# mmu6100x.net
KiCad netlist of a schematic drawn in EAGLE
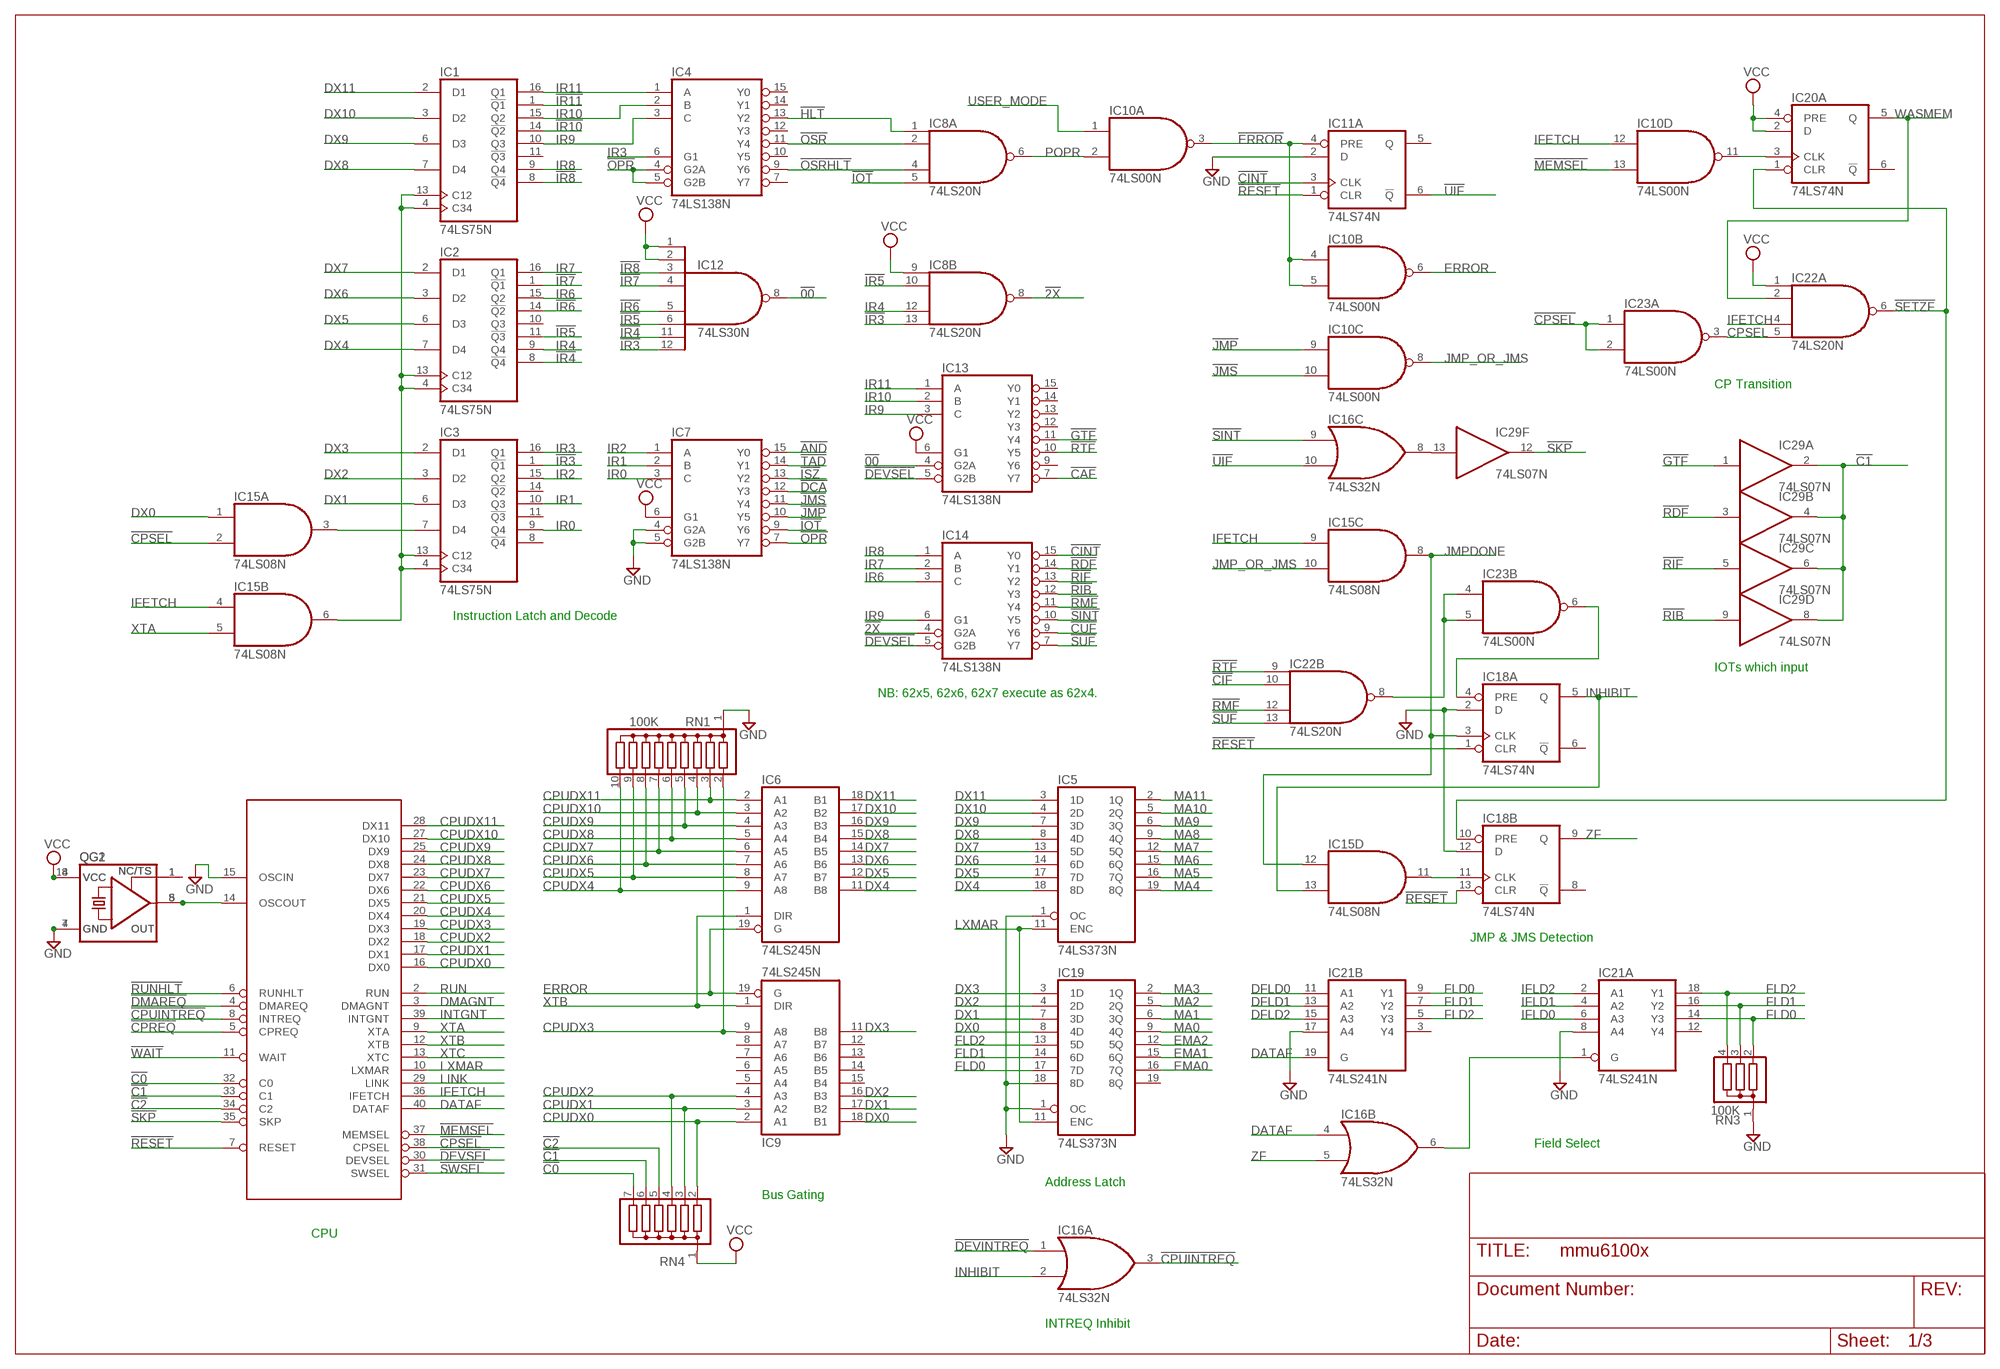
[diagram p0: schematic, sheet 1]
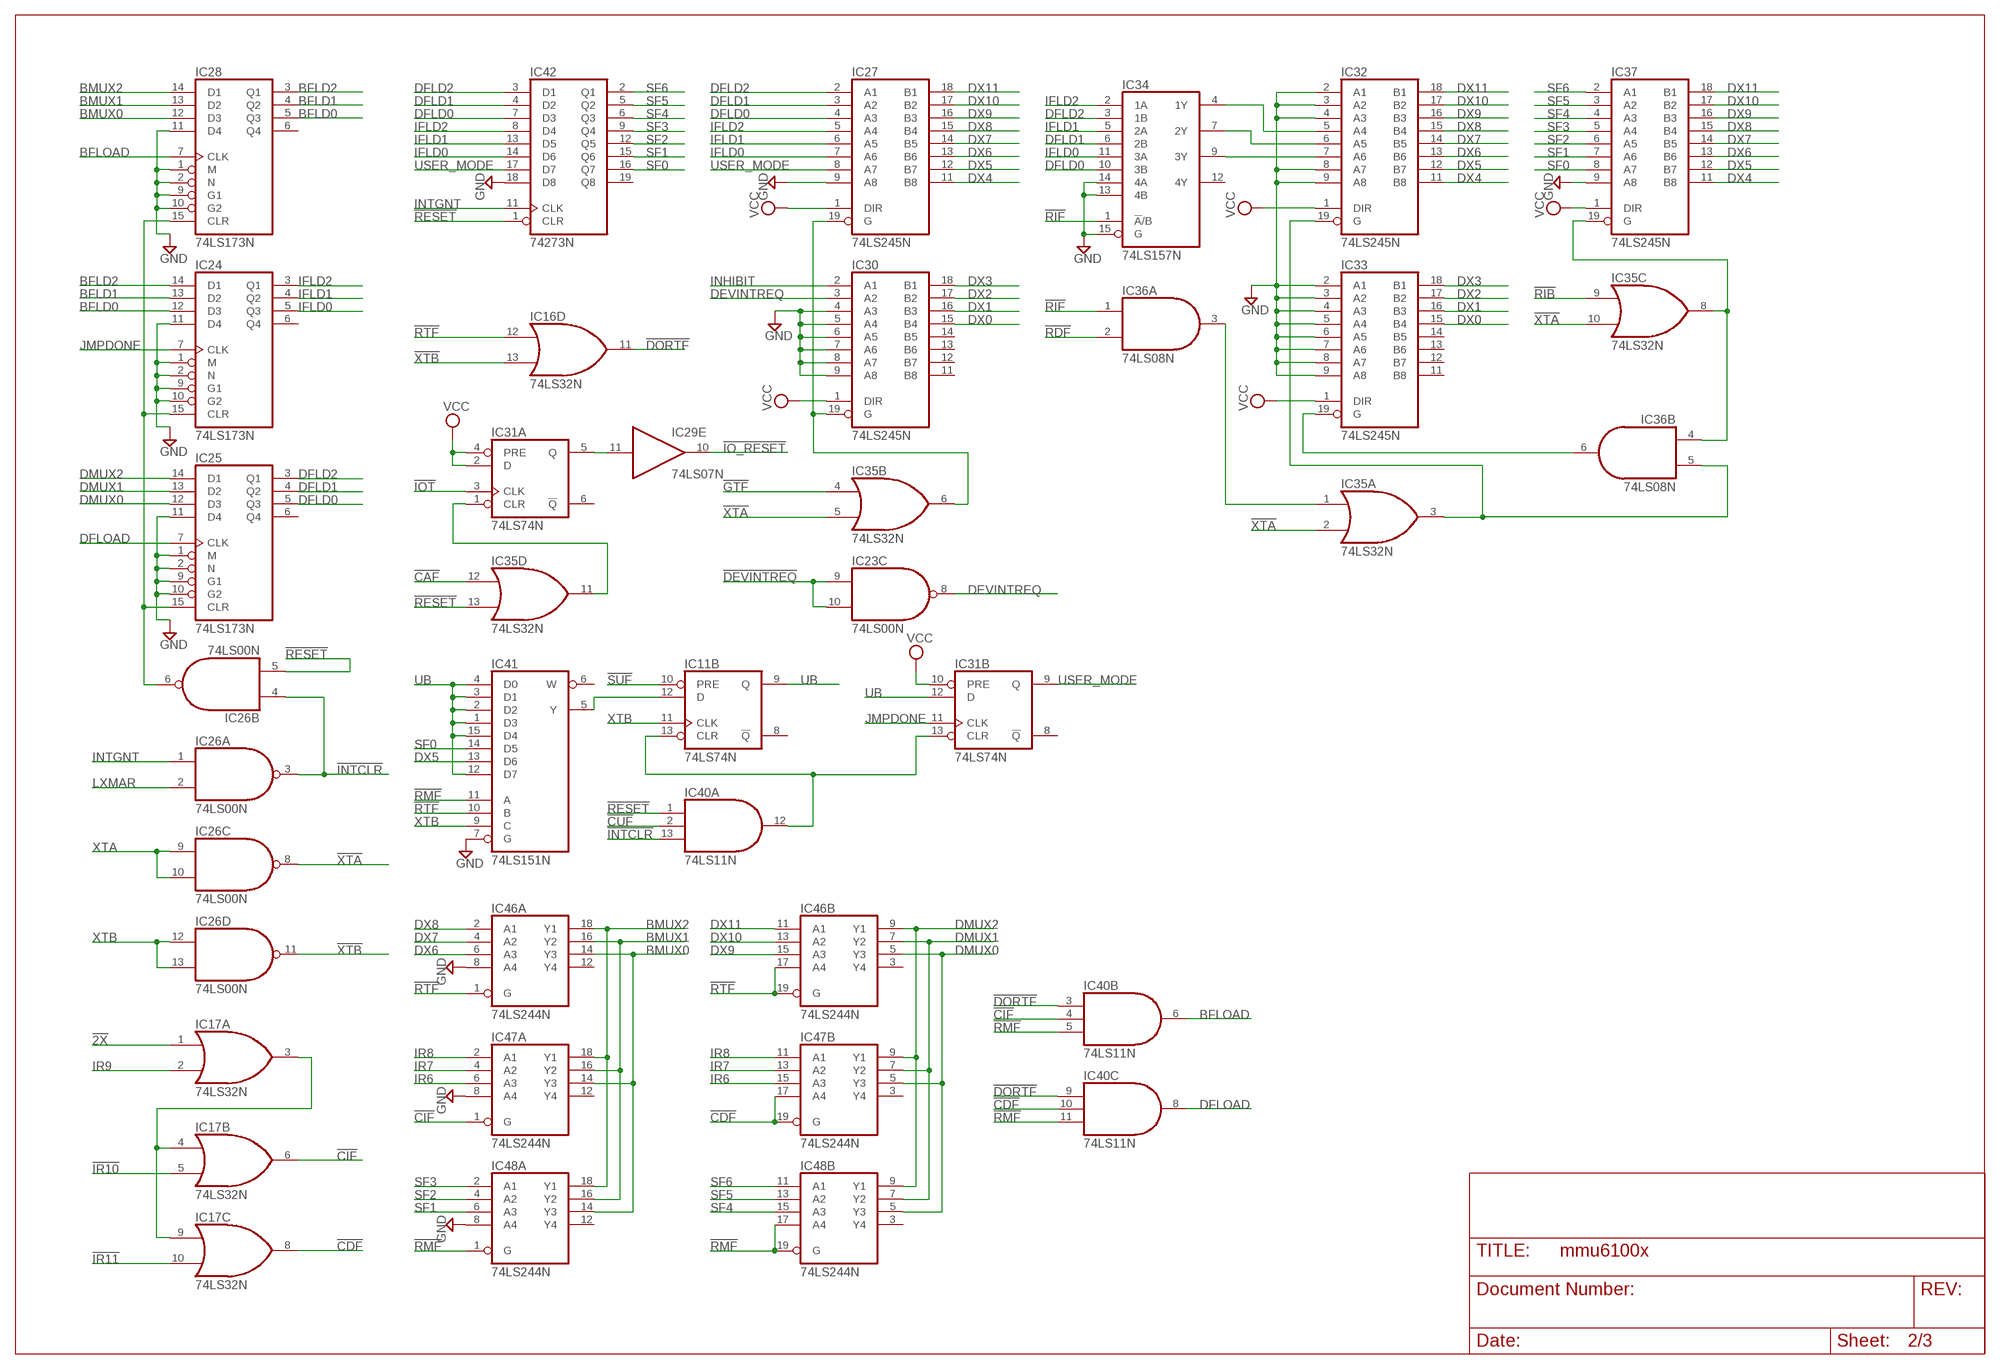
[diagram p1: schematic, sheet 2]
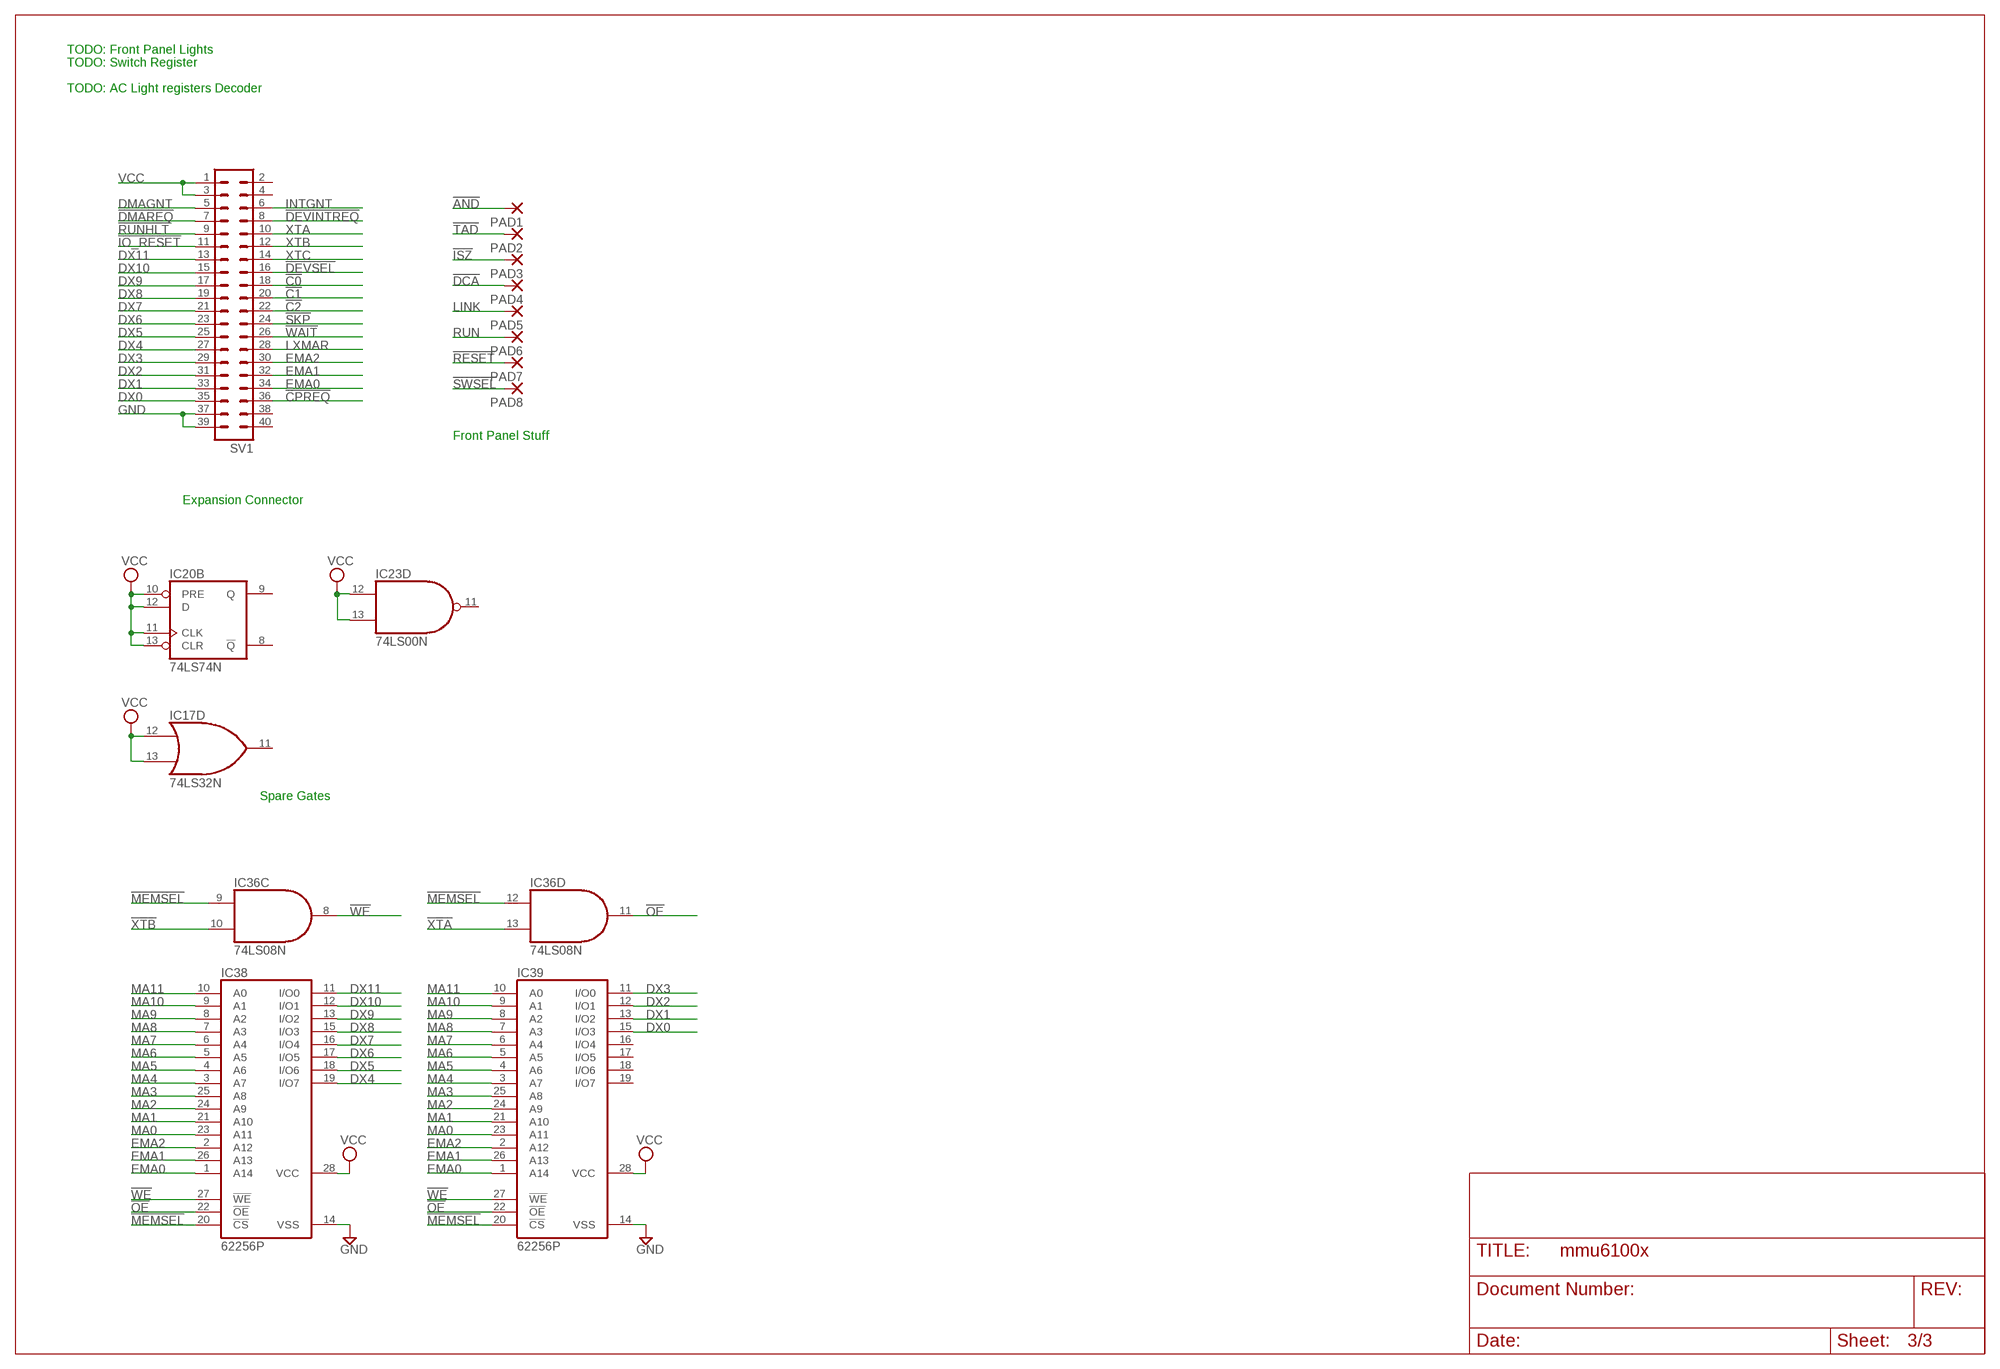
[diagram p2: schematic, sheet 3]

(export (version "E")
  (design (tool "Eeschema 10.0.6"))
  (components
    (comp (ref "IC11")
      (value "74LS74N")
      (footprint "eagle-import:DIL14")
      (libsource (lib "eagle-import") (part "7474NLS"))
    )
    (comp (ref "IC16")
      (value "74LS32N")
      (footprint "eagle-import:DIL14")
      (libsource (lib "eagle-import") (part "7432NLS"))
    )
    (comp (ref "IC17")
      (value "74LS32N")
      (footprint "eagle-import:DIL14")
      (libsource (lib "eagle-import") (part "7432NLS"))
    )
    (comp (ref "IC23")
      (value "74LS00N")
      (footprint "eagle-import:DIL14")
      (libsource (lib "eagle-import") (part "7400NLS"))
    )
    (comp (ref "IC24")
      (value "74LS173N")
      (footprint "eagle-import:DIL16")
      (libsource (lib "eagle-import") (part "74173NLS"))
    )
    (comp (ref "IC25")
      (value "74LS173N")
      (footprint "eagle-import:DIL16")
      (libsource (lib "eagle-import") (part "74173NLS"))
    )
    (comp (ref "IC26")
      (value "74LS00N")
      (footprint "eagle-import:DIL14")
      (libsource (lib "eagle-import") (part "7400NLS"))
    )
    (comp (ref "IC27")
      (value "74LS245N")
      (footprint "eagle-import:DIL20")
      (libsource (lib "eagle-import") (part "74245NLS"))
    )
    (comp (ref "IC28")
      (value "74LS173N")
      (footprint "eagle-import:DIL16")
      (libsource (lib "eagle-import") (part "74173NLS"))
    )
    (comp (ref "IC29")
      (value "74LS07N")
      (footprint "eagle-import:DIL14")
      (libsource (lib "eagle-import") (part "7407NLS"))
    )
    (comp (ref "IC30")
      (value "74LS245N")
      (footprint "eagle-import:DIL20")
      (libsource (lib "eagle-import") (part "74245NLS"))
    )
    (comp (ref "IC31")
      (value "74LS74N")
      (footprint "eagle-import:DIL14")
      (libsource (lib "eagle-import") (part "7474NLS"))
    )
    (comp (ref "IC32")
      (value "74LS245N")
      (footprint "eagle-import:DIL20")
      (libsource (lib "eagle-import") (part "74245NLS"))
    )
    (comp (ref "IC33")
      (value "74LS245N")
      (footprint "eagle-import:DIL20")
      (libsource (lib "eagle-import") (part "74245NLS"))
    )
    (comp (ref "IC34")
      (value "74LS157N")
      (footprint "eagle-import:DIL16")
      (libsource (lib "eagle-import") (part "74157NLS"))
    )
    (comp (ref "IC35")
      (value "74LS32N")
      (footprint "eagle-import:DIL14")
      (libsource (lib "eagle-import") (part "7432NLS"))
    )
    (comp (ref "IC36")
      (value "74LS08N")
      (footprint "eagle-import:DIL14")
      (libsource (lib "eagle-import") (part "7408NLS"))
    )
    (comp (ref "IC37")
      (value "74LS245N")
      (footprint "eagle-import:DIL20")
      (libsource (lib "eagle-import") (part "74245NLS"))
    )
    (comp (ref "IC40")
      (value "74LS11N")
      (footprint "eagle-import:DIL14")
      (libsource (lib "eagle-import") (part "7411NLS"))
    )
    (comp (ref "IC41")
      (value "74LS151N")
      (footprint "eagle-import:DIL16")
      (libsource (lib "eagle-import") (part "74151NLS"))
    )
    (comp (ref "IC42")
      (value "74273N")
      (footprint "eagle-import:DIL20")
      (libsource (lib "eagle-import") (part "74273N"))
    )
    (comp (ref "IC46")
      (value "74LS244N")
      (footprint "eagle-import:DIL20")
      (libsource (lib "eagle-import") (part "74244NLS"))
    )
    (comp (ref "IC47")
      (value "74LS244N")
      (footprint "eagle-import:DIL20")
      (libsource (lib "eagle-import") (part "74244NLS"))
    )
    (comp (ref "IC48")
      (value "74LS244N")
      (footprint "eagle-import:DIL20")
      (libsource (lib "eagle-import") (part "74244NLS"))
    )
    (comp (ref "IC20")
      (value "74LS74N")
      (footprint "eagle-import:DIL14")
      (libsource (lib "eagle-import") (part "7474NLS"))
    )
    (comp (ref "IC38")
      (value "62256P")
      (footprint "eagle-import:DIL28-6")
      (libsource (lib "eagle-import") (part "62256P"))
    )
    (comp (ref "IC39")
      (value "62256P")
      (footprint "eagle-import:DIL28-6")
      (libsource (lib "eagle-import") (part "62256P"))
    )
    (comp (ref "PAD1")
      (value "2,15/1,0")
      (footprint "eagle-import:2,15_1,0")
      (libsource (lib "eagle-import") (part "2,15/1,0"))
    )
    (comp (ref "PAD2")
      (value "2,15/1,0")
      (footprint "eagle-import:2,15_1,0")
      (libsource (lib "eagle-import") (part "2,15/1,0"))
    )
    (comp (ref "PAD3")
      (value "2,15/1,0")
      (footprint "eagle-import:2,15_1,0")
      (libsource (lib "eagle-import") (part "2,15/1,0"))
    )
    (comp (ref "PAD4")
      (value "2,15/1,0")
      (footprint "eagle-import:2,15_1,0")
      (libsource (lib "eagle-import") (part "2,15/1,0"))
    )
    (comp (ref "PAD5")
      (value "2,15/1,0")
      (footprint "eagle-import:2,15_1,0")
      (libsource (lib "eagle-import") (part "2,15/1,0"))
    )
    (comp (ref "PAD6")
      (value "2,15/1,0")
      (footprint "eagle-import:2,15_1,0")
      (libsource (lib "eagle-import") (part "2,15/1,0"))
    )
    (comp (ref "PAD7")
      (value "2,15/1,0")
      (footprint "eagle-import:2,15_1,0")
      (libsource (lib "eagle-import") (part "2,15/1,0"))
    )
    (comp (ref "PAD8")
      (value "2,15/1,0")
      (footprint "eagle-import:2,15_1,0")
      (libsource (lib "eagle-import") (part "2,15/1,0"))
    )
    (comp (ref "SV1")
      (value "MA20-2")
      (footprint "eagle-import:MA20-2")
      (libsource (lib "eagle-import") (part "MA20-2"))
    )
    (comp (ref "CPU")
      (value "IM6100")
      (footprint "eagle-import:DIL40")
      (libsource (lib "eagle-import") (part "IM6100"))
    )
    (comp (ref "IC1")
      (value "74LS75N")
      (footprint "eagle-import:DIL16")
      (libsource (lib "eagle-import") (part "7475NLS"))
    )
    (comp (ref "IC2")
      (value "74LS75N")
      (footprint "eagle-import:DIL16")
      (libsource (lib "eagle-import") (part "7475NLS"))
    )
    (comp (ref "IC3")
      (value "74LS75N")
      (footprint "eagle-import:DIL16")
      (libsource (lib "eagle-import") (part "7475NLS"))
    )
    (comp (ref "IC4")
      (value "74LS138N")
      (footprint "eagle-import:DIL16")
      (libsource (lib "eagle-import") (part "74138NLS"))
    )
    (comp (ref "IC5")
      (value "74LS373N")
      (footprint "eagle-import:DIL20")
      (libsource (lib "eagle-import") (part "74373NLS"))
    )
    (comp (ref "IC6")
      (value "74LS245N")
      (footprint "eagle-import:DIL20")
      (libsource (lib "eagle-import") (part "74245NLS"))
    )
    (comp (ref "IC7")
      (value "74LS138N")
      (footprint "eagle-import:DIL16")
      (libsource (lib "eagle-import") (part "74138NLS"))
    )
    (comp (ref "IC8")
      (value "74LS20N")
      (footprint "eagle-import:DIL14")
      (libsource (lib "eagle-import") (part "7420NLS"))
    )
    (comp (ref "IC9")
      (value "74LS245N")
      (footprint "eagle-import:DIL20")
      (libsource (lib "eagle-import") (part "74245NLS"))
    )
    (comp (ref "IC10")
      (value "74LS00N")
      (footprint "eagle-import:DIL14")
      (libsource (lib "eagle-import") (part "7400NLS"))
    )
    (comp (ref "IC12")
      (value "74LS30N")
      (footprint "eagle-import:DIL14")
      (libsource (lib "eagle-import") (part "7430NLS"))
    )
    (comp (ref "IC13")
      (value "74LS138N")
      (footprint "eagle-import:DIL16")
      (libsource (lib "eagle-import") (part "74138NLS"))
    )
    (comp (ref "IC14")
      (value "74LS138N")
      (footprint "eagle-import:DIL16")
      (libsource (lib "eagle-import") (part "74138NLS"))
    )
    (comp (ref "IC15")
      (value "74LS08N")
      (footprint "eagle-import:DIL14")
      (libsource (lib "eagle-import") (part "7408NLS"))
    )
    (comp (ref "IC18")
      (value "74LS74N")
      (footprint "eagle-import:DIL14")
      (libsource (lib "eagle-import") (part "7474NLS"))
    )
    (comp (ref "IC19")
      (value "74LS373N")
      (footprint "eagle-import:DIL20")
      (libsource (lib "eagle-import") (part "74373NLS"))
    )
    (comp (ref "IC21")
      (value "74LS241N")
      (footprint "eagle-import:DIL20")
      (libsource (lib "eagle-import") (part "74241NLS"))
    )
    (comp (ref "IC22")
      (value "74LS20N")
      (footprint "eagle-import:DIL14")
      (libsource (lib "eagle-import") (part "7420NLS"))
    )
    (comp (ref "QG1")
      (value "XO-8")
      (footprint "eagle-import:DIL08S")
      (libsource (lib "eagle-import") (part "XO-8"))
    )
    (comp (ref "QG2")
      (value "XO-14")
      (footprint "eagle-import:DIL14S")
      (libsource (lib "eagle-import") (part "XO-14"))
    )
    (comp (ref "RN1")
      (value "100K")
      (footprint "eagle-import:SIL10")
      (libsource (lib "eagle-import") (part "G09R"))
    )
    (comp (ref "RN3")
      (value "100K")
      (footprint "eagle-import:SIL4")
      (libsource (lib "eagle-import") (part "G03R"))
    )
    (comp (ref "RN4")
      (value "G06R")
      (footprint "eagle-import:SIL7")
      (libsource (lib "eagle-import") (part "G06R"))
    )
  )
  (nets
    (net (code "1") (name "BFLD0") (class "Default")
      (node (ref "IC24") (pin "12") (pinfunction "D3_12") (pintype "input"))
      (node (ref "IC28") (pin "5") (pinfunction "Q3_5") (pintype "tri_state"))
    )
    (net (code "2") (name "BFLD1") (class "Default")
      (node (ref "IC24") (pin "13") (pinfunction "D2_13") (pintype "input"))
      (node (ref "IC28") (pin "4") (pinfunction "Q2_4") (pintype "tri_state"))
    )
    (net (code "3") (name "BFLD2") (class "Default")
      (node (ref "IC24") (pin "14") (pinfunction "D1_14") (pintype "input"))
      (node (ref "IC28") (pin "3") (pinfunction "Q1_3") (pintype "tri_state"))
    )
    (net (code "4") (name "BFLOAD") (class "Default")
      (node (ref "IC28") (pin "7") (pinfunction "CLK_7") (pintype "input"))
      (node (ref "IC40") (pin "6") (pinfunction "O_6") (pintype "output"))
    )
    (net (code "5") (name "BMUX0") (class "Default")
      (node (ref "IC28") (pin "12") (pinfunction "D3_12") (pintype "input"))
      (node (ref "IC46") (pin "14") (pinfunction "Y3_14") (pintype "tri_state"))
      (node (ref "IC47") (pin "14") (pinfunction "Y3_14") (pintype "tri_state"))
      (node (ref "IC48") (pin "14") (pinfunction "Y3_14") (pintype "tri_state"))
    )
    (net (code "6") (name "BMUX1") (class "Default")
      (node (ref "IC28") (pin "13") (pinfunction "D2_13") (pintype "input"))
      (node (ref "IC46") (pin "16") (pinfunction "Y2_16") (pintype "tri_state"))
      (node (ref "IC47") (pin "16") (pinfunction "Y2_16") (pintype "tri_state"))
      (node (ref "IC48") (pin "16") (pinfunction "Y2_16") (pintype "tri_state"))
    )
    (net (code "7") (name "BMUX2") (class "Default")
      (node (ref "IC28") (pin "14") (pinfunction "D1_14") (pintype "input"))
      (node (ref "IC46") (pin "18") (pinfunction "Y1_18") (pintype "tri_state"))
      (node (ref "IC47") (pin "18") (pinfunction "Y1_18") (pintype "tri_state"))
      (node (ref "IC48") (pin "18") (pinfunction "Y1_18") (pintype "tri_state"))
    )
    (net (code "8") (name "CPSEL") (class "Default")
      (node (ref "IC22") (pin "5") (pinfunction "I3_5") (pintype "input"))
      (node (ref "IC23") (pin "3") (pinfunction "O_3") (pintype "output"))
    )
    (net (code "9") (name "CPUDX0") (class "Default")
      (node (ref "CPU") (pin "16") (pinfunction "DX0_16") (pintype "bidirectional"))
      (node (ref "IC9") (pin "2") (pinfunction "A1_2") (pintype "bidirectional"))
      (node (ref "RN4") (pin "2") (pinfunction "2_2") (pintype "passive"))
    )
    (net (code "10") (name "CPUDX1") (class "Default")
      (node (ref "CPU") (pin "17") (pinfunction "DX1_17") (pintype "bidirectional"))
      (node (ref "IC9") (pin "3") (pinfunction "A2_3") (pintype "bidirectional"))
      (node (ref "RN4") (pin "3") (pinfunction "3_3") (pintype "passive"))
    )
    (net (code "11") (name "CPUDX2") (class "Default")
      (node (ref "CPU") (pin "18") (pinfunction "DX2_18") (pintype "bidirectional"))
      (node (ref "IC9") (pin "4") (pinfunction "A3_4") (pintype "bidirectional"))
      (node (ref "RN4") (pin "4") (pinfunction "4_4") (pintype "passive"))
    )
    (net (code "12") (name "CPUDX3") (class "Default")
      (node (ref "CPU") (pin "19") (pinfunction "DX3_19") (pintype "bidirectional"))
      (node (ref "IC9") (pin "9") (pinfunction "A8_9") (pintype "bidirectional"))
      (node (ref "RN1") (pin "2") (pinfunction "2_2") (pintype "passive"))
    )
    (net (code "13") (name "CPUDX4") (class "Default")
      (node (ref "CPU") (pin "20") (pinfunction "DX4_20") (pintype "bidirectional"))
      (node (ref "IC6") (pin "9") (pinfunction "A8_9") (pintype "bidirectional"))
      (node (ref "RN1") (pin "10") (pinfunction "10_10") (pintype "passive"))
    )
    (net (code "14") (name "CPUDX5") (class "Default")
      (node (ref "CPU") (pin "21") (pinfunction "DX5_21") (pintype "bidirectional"))
      (node (ref "IC6") (pin "8") (pinfunction "A7_8") (pintype "bidirectional"))
      (node (ref "RN1") (pin "9") (pinfunction "9_9") (pintype "passive"))
    )
    (net (code "15") (name "CPUDX6") (class "Default")
      (node (ref "CPU") (pin "22") (pinfunction "DX6_22") (pintype "bidirectional"))
      (node (ref "IC6") (pin "7") (pinfunction "A6_7") (pintype "bidirectional"))
      (node (ref "RN1") (pin "8") (pinfunction "8_8") (pintype "passive"))
    )
    (net (code "16") (name "CPUDX7") (class "Default")
      (node (ref "CPU") (pin "23") (pinfunction "DX7_23") (pintype "bidirectional"))
      (node (ref "IC6") (pin "6") (pinfunction "A5_6") (pintype "bidirectional"))
      (node (ref "RN1") (pin "7") (pinfunction "7_7") (pintype "passive"))
    )
    (net (code "17") (name "CPUDX8") (class "Default")
      (node (ref "CPU") (pin "24") (pinfunction "DX8_24") (pintype "bidirectional"))
      (node (ref "IC6") (pin "5") (pinfunction "A4_5") (pintype "bidirectional"))
      (node (ref "RN1") (pin "6") (pinfunction "6_6") (pintype "passive"))
    )
    (net (code "18") (name "CPUDX9") (class "Default")
      (node (ref "CPU") (pin "25") (pinfunction "DX9_25") (pintype "bidirectional"))
      (node (ref "IC6") (pin "4") (pinfunction "A3_4") (pintype "bidirectional"))
      (node (ref "RN1") (pin "5") (pinfunction "5_5") (pintype "passive"))
    )
    (net (code "19") (name "CPUDX10") (class "Default")
      (node (ref "CPU") (pin "27") (pinfunction "DX10_27") (pintype "bidirectional"))
      (node (ref "IC6") (pin "3") (pinfunction "A2_3") (pintype "bidirectional"))
      (node (ref "RN1") (pin "4") (pinfunction "4_4") (pintype "passive"))
    )
    (net (code "20") (name "CPUDX11") (class "Default")
      (node (ref "CPU") (pin "28") (pinfunction "DX11_28") (pintype "bidirectional"))
      (node (ref "IC6") (pin "2") (pinfunction "A1_2") (pintype "bidirectional"))
      (node (ref "RN1") (pin "3") (pinfunction "3_3") (pintype "passive"))
    )
    (net (code "21") (name "DATAF") (class "Default")
      (node (ref "CPU") (pin "40") (pinfunction "DATAF_40") (pintype "output"))
      (node (ref "IC16") (pin "4") (pinfunction "I0_4") (pintype "input"))
      (node (ref "IC21") (pin "19") (pinfunction "G_19") (pintype "input"))
    )
    (net (code "22") (name "DEVINTREQ") (class "Default")
      (node (ref "IC23") (pin "8") (pinfunction "O_8") (pintype "output"))
      (node (ref "IC30") (pin "3") (pinfunction "A2_3") (pintype "bidirectional"))
    )
    (net (code "23") (name "DFLD0") (class "Default")
      (node (ref "IC21") (pin "11") (pinfunction "A1_11") (pintype "input"))
      (node (ref "IC25") (pin "5") (pinfunction "Q3_5") (pintype "tri_state"))
      (node (ref "IC27") (pin "4") (pinfunction "A3_4") (pintype "bidirectional"))
      (node (ref "IC34") (pin "10") (pinfunction "3B_10") (pintype "input"))
      (node (ref "IC42") (pin "7") (pinfunction "D3_7") (pintype "input"))
    )
    (net (code "24") (name "DFLD1") (class "Default")
      (node (ref "IC21") (pin "13") (pinfunction "A2_13") (pintype "input"))
      (node (ref "IC25") (pin "4") (pinfunction "Q2_4") (pintype "tri_state"))
      (node (ref "IC27") (pin "3") (pinfunction "A2_3") (pintype "bidirectional"))
      (node (ref "IC34") (pin "6") (pinfunction "2B_6") (pintype "input"))
      (node (ref "IC42") (pin "4") (pinfunction "D2_4") (pintype "input"))
    )
    (net (code "25") (name "DFLD2") (class "Default")
      (node (ref "IC21") (pin "15") (pinfunction "A3_15") (pintype "input"))
      (node (ref "IC25") (pin "3") (pinfunction "Q1_3") (pintype "tri_state"))
      (node (ref "IC27") (pin "2") (pinfunction "A1_2") (pintype "bidirectional"))
      (node (ref "IC34") (pin "3") (pinfunction "1B_3") (pintype "input"))
      (node (ref "IC42") (pin "3") (pinfunction "D1_3") (pintype "input"))
    )
    (net (code "26") (name "DFLOAD") (class "Default")
      (node (ref "IC25") (pin "7") (pinfunction "CLK_7") (pintype "input"))
      (node (ref "IC40") (pin "8") (pinfunction "O_8") (pintype "output"))
    )
    (net (code "27") (name "DMAGNT") (class "Default")
      (node (ref "CPU") (pin "3") (pinfunction "DMAGNT_3") (pintype "output"))
      (node (ref "SV1") (pin "5") (pinfunction "5_5") (pintype "passive"))
    )
    (net (code "28") (name "DMUX0") (class "Default")
      (node (ref "IC25") (pin "12") (pinfunction "D3_12") (pintype "input"))
      (node (ref "IC46") (pin "5") (pinfunction "Y3_5") (pintype "tri_state"))
      (node (ref "IC47") (pin "5") (pinfunction "Y3_5") (pintype "tri_state"))
      (node (ref "IC48") (pin "5") (pinfunction "Y3_5") (pintype "tri_state"))
    )
    (net (code "29") (name "DMUX1") (class "Default")
      (node (ref "IC25") (pin "13") (pinfunction "D2_13") (pintype "input"))
      (node (ref "IC46") (pin "7") (pinfunction "Y2_7") (pintype "tri_state"))
      (node (ref "IC47") (pin "7") (pinfunction "Y2_7") (pintype "tri_state"))
      (node (ref "IC48") (pin "7") (pinfunction "Y2_7") (pintype "tri_state"))
    )
    (net (code "30") (name "DMUX2") (class "Default")
      (node (ref "IC25") (pin "14") (pinfunction "D1_14") (pintype "input"))
      (node (ref "IC46") (pin "9") (pinfunction "Y1_9") (pintype "tri_state"))
      (node (ref "IC47") (pin "9") (pinfunction "Y1_9") (pintype "tri_state"))
      (node (ref "IC48") (pin "9") (pinfunction "Y1_9") (pintype "tri_state"))
    )
    (net (code "31") (name "DX0") (class "Default")
      (node (ref "IC15") (pin "1") (pinfunction "I0_1") (pintype "input"))
      (node (ref "IC19") (pin "8") (pinfunction "4D_8") (pintype "input"))
      (node (ref "IC30") (pin "15") (pinfunction "B4_15") (pintype "bidirectional"))
      (node (ref "IC33") (pin "15") (pinfunction "B4_15") (pintype "bidirectional"))
      (node (ref "IC39") (pin "15") (pinfunction "I/O3_15") (pintype "bidirectional"))
      (node (ref "IC9") (pin "18") (pinfunction "B1_18") (pintype "bidirectional"))
      (node (ref "SV1") (pin "35") (pinfunction "35_35") (pintype "passive"))
    )
    (net (code "32") (name "DX1") (class "Default")
      (node (ref "IC19") (pin "7") (pinfunction "3D_7") (pintype "input"))
      (node (ref "IC3") (pin "6") (pinfunction "D3_6") (pintype "input"))
      (node (ref "IC30") (pin "16") (pinfunction "B3_16") (pintype "bidirectional"))
      (node (ref "IC33") (pin "16") (pinfunction "B3_16") (pintype "bidirectional"))
      (node (ref "IC39") (pin "13") (pinfunction "I/O2_13") (pintype "bidirectional"))
      (node (ref "IC9") (pin "17") (pinfunction "B2_17") (pintype "bidirectional"))
      (node (ref "SV1") (pin "33") (pinfunction "33_33") (pintype "passive"))
    )
    (net (code "33") (name "DX2") (class "Default")
      (node (ref "IC19") (pin "4") (pinfunction "2D_4") (pintype "input"))
      (node (ref "IC3") (pin "3") (pinfunction "D2_3") (pintype "input"))
      (node (ref "IC30") (pin "17") (pinfunction "B2_17") (pintype "bidirectional"))
      (node (ref "IC33") (pin "17") (pinfunction "B2_17") (pintype "bidirectional"))
      (node (ref "IC39") (pin "12") (pinfunction "I/O1_12") (pintype "bidirectional"))
      (node (ref "IC9") (pin "16") (pinfunction "B3_16") (pintype "bidirectional"))
      (node (ref "SV1") (pin "31") (pinfunction "31_31") (pintype "passive"))
    )
    (net (code "34") (name "DX3") (class "Default")
      (node (ref "IC19") (pin "3") (pinfunction "1D_3") (pintype "input"))
      (node (ref "IC3") (pin "2") (pinfunction "D1_2") (pintype "input"))
      (node (ref "IC30") (pin "18") (pinfunction "B1_18") (pintype "bidirectional"))
      (node (ref "IC33") (pin "18") (pinfunction "B1_18") (pintype "bidirectional"))
      (node (ref "IC39") (pin "11") (pinfunction "I/O0_11") (pintype "bidirectional"))
      (node (ref "IC9") (pin "11") (pinfunction "B8_11") (pintype "bidirectional"))
      (node (ref "SV1") (pin "29") (pinfunction "29_29") (pintype "passive"))
    )
    (net (code "35") (name "DX4") (class "Default")
      (node (ref "IC2") (pin "7") (pinfunction "D4_7") (pintype "input"))
      (node (ref "IC27") (pin "11") (pinfunction "B8_11") (pintype "bidirectional"))
      (node (ref "IC32") (pin "11") (pinfunction "B8_11") (pintype "bidirectional"))
      (node (ref "IC37") (pin "11") (pinfunction "B8_11") (pintype "bidirectional"))
      (node (ref "IC38") (pin "19") (pinfunction "I/O7_19") (pintype "bidirectional"))
      (node (ref "IC5") (pin "18") (pinfunction "8D_18") (pintype "input"))
      (node (ref "IC6") (pin "11") (pinfunction "B8_11") (pintype "bidirectional"))
      (node (ref "SV1") (pin "27") (pinfunction "27_27") (pintype "passive"))
    )
    (net (code "36") (name "DX5") (class "Default")
      (node (ref "IC2") (pin "6") (pinfunction "D3_6") (pintype "input"))
      (node (ref "IC27") (pin "12") (pinfunction "B7_12") (pintype "bidirectional"))
      (node (ref "IC32") (pin "12") (pinfunction "B7_12") (pintype "bidirectional"))
      (node (ref "IC37") (pin "12") (pinfunction "B7_12") (pintype "bidirectional"))
      (node (ref "IC38") (pin "18") (pinfunction "I/O6_18") (pintype "bidirectional"))
      (node (ref "IC41") (pin "13") (pinfunction "D6_13") (pintype "input"))
      (node (ref "IC5") (pin "17") (pinfunction "7D_17") (pintype "input"))
      (node (ref "IC6") (pin "12") (pinfunction "B7_12") (pintype "bidirectional"))
      (node (ref "SV1") (pin "25") (pinfunction "25_25") (pintype "passive"))
    )
    (net (code "37") (name "DX6") (class "Default")
      (node (ref "IC2") (pin "3") (pinfunction "D2_3") (pintype "input"))
      (node (ref "IC27") (pin "13") (pinfunction "B6_13") (pintype "bidirectional"))
      (node (ref "IC32") (pin "13") (pinfunction "B6_13") (pintype "bidirectional"))
      (node (ref "IC37") (pin "13") (pinfunction "B6_13") (pintype "bidirectional"))
      (node (ref "IC38") (pin "17") (pinfunction "I/O5_17") (pintype "bidirectional"))
      (node (ref "IC46") (pin "6") (pinfunction "A3_6") (pintype "input"))
      (node (ref "IC5") (pin "14") (pinfunction "6D_14") (pintype "input"))
      (node (ref "IC6") (pin "13") (pinfunction "B6_13") (pintype "bidirectional"))
      (node (ref "SV1") (pin "23") (pinfunction "23_23") (pintype "passive"))
    )
    (net (code "38") (name "DX7") (class "Default")
      (node (ref "IC2") (pin "2") (pinfunction "D1_2") (pintype "input"))
      (node (ref "IC27") (pin "14") (pinfunction "B5_14") (pintype "bidirectional"))
      (node (ref "IC32") (pin "14") (pinfunction "B5_14") (pintype "bidirectional"))
      (node (ref "IC37") (pin "14") (pinfunction "B5_14") (pintype "bidirectional"))
      (node (ref "IC38") (pin "16") (pinfunction "I/O4_16") (pintype "bidirectional"))
      (node (ref "IC46") (pin "4") (pinfunction "A2_4") (pintype "input"))
      (node (ref "IC5") (pin "13") (pinfunction "5D_13") (pintype "input"))
      (node (ref "IC6") (pin "14") (pinfunction "B5_14") (pintype "bidirectional"))
      (node (ref "SV1") (pin "21") (pinfunction "21_21") (pintype "passive"))
    )
    (net (code "39") (name "DX8") (class "Default")
      (node (ref "IC1") (pin "7") (pinfunction "D4_7") (pintype "input"))
      (node (ref "IC27") (pin "15") (pinfunction "B4_15") (pintype "bidirectional"))
      (node (ref "IC32") (pin "15") (pinfunction "B4_15") (pintype "bidirectional"))
      (node (ref "IC37") (pin "15") (pinfunction "B4_15") (pintype "bidirectional"))
      (node (ref "IC38") (pin "15") (pinfunction "I/O3_15") (pintype "bidirectional"))
      (node (ref "IC46") (pin "2") (pinfunction "A1_2") (pintype "input"))
      (node (ref "IC5") (pin "8") (pinfunction "4D_8") (pintype "input"))
      (node (ref "IC6") (pin "15") (pinfunction "B4_15") (pintype "bidirectional"))
      (node (ref "SV1") (pin "19") (pinfunction "19_19") (pintype "passive"))
    )
    (net (code "40") (name "DX9") (class "Default")
      (node (ref "IC1") (pin "6") (pinfunction "D3_6") (pintype "input"))
      (node (ref "IC27") (pin "16") (pinfunction "B3_16") (pintype "bidirectional"))
      (node (ref "IC32") (pin "16") (pinfunction "B3_16") (pintype "bidirectional"))
      (node (ref "IC37") (pin "16") (pinfunction "B3_16") (pintype "bidirectional"))
      (node (ref "IC38") (pin "13") (pinfunction "I/O2_13") (pintype "bidirectional"))
      (node (ref "IC46") (pin "15") (pinfunction "A3_15") (pintype "input"))
      (node (ref "IC5") (pin "7") (pinfunction "3D_7") (pintype "input"))
      (node (ref "IC6") (pin "16") (pinfunction "B3_16") (pintype "bidirectional"))
      (node (ref "SV1") (pin "17") (pinfunction "17_17") (pintype "passive"))
    )
    (net (code "41") (name "DX10") (class "Default")
      (node (ref "IC1") (pin "3") (pinfunction "D2_3") (pintype "input"))
      (node (ref "IC27") (pin "17") (pinfunction "B2_17") (pintype "bidirectional"))
      (node (ref "IC32") (pin "17") (pinfunction "B2_17") (pintype "bidirectional"))
      (node (ref "IC37") (pin "17") (pinfunction "B2_17") (pintype "bidirectional"))
      (node (ref "IC38") (pin "12") (pinfunction "I/O1_12") (pintype "bidirectional"))
      (node (ref "IC46") (pin "13") (pinfunction "A2_13") (pintype "input"))
      (node (ref "IC5") (pin "4") (pinfunction "2D_4") (pintype "input"))
      (node (ref "IC6") (pin "17") (pinfunction "B2_17") (pintype "bidirectional"))
      (node (ref "SV1") (pin "15") (pinfunction "15_15") (pintype "passive"))
    )
    (net (code "42") (name "DX11") (class "Default")
      (node (ref "IC1") (pin "2") (pinfunction "D1_2") (pintype "input"))
      (node (ref "IC27") (pin "18") (pinfunction "B1_18") (pintype "bidirectional"))
      (node (ref "IC32") (pin "18") (pinfunction "B1_18") (pintype "bidirectional"))
      (node (ref "IC37") (pin "18") (pinfunction "B1_18") (pintype "bidirectional"))
      (node (ref "IC38") (pin "11") (pinfunction "I/O0_11") (pintype "bidirectional"))
      (node (ref "IC46") (pin "11") (pinfunction "A1_11") (pintype "input"))
      (node (ref "IC5") (pin "3") (pinfunction "1D_3") (pintype "input"))
      (node (ref "IC6") (pin "18") (pinfunction "B1_18") (pintype "bidirectional"))
      (node (ref "SV1") (pin "13") (pinfunction "13_13") (pintype "passive"))
    )
    (net (code "43") (name "EMA0") (class "Default")
      (node (ref "IC19") (pin "16") (pinfunction "7Q_16") (pintype "tri_state"))
      (node (ref "IC38") (pin "1") (pinfunction "A14_1") (pintype "input"))
      (node (ref "IC39") (pin "1") (pinfunction "A14_1") (pintype "input"))
      (node (ref "SV1") (pin "34") (pinfunction "34_34") (pintype "passive"))
    )
    (net (code "44") (name "EMA1") (class "Default")
      (node (ref "IC19") (pin "15") (pinfunction "6Q_15") (pintype "tri_state"))
      (node (ref "IC38") (pin "26") (pinfunction "A13_26") (pintype "input"))
      (node (ref "IC39") (pin "26") (pinfunction "A13_26") (pintype "input"))
      (node (ref "SV1") (pin "32") (pinfunction "32_32") (pintype "passive"))
    )
    (net (code "45") (name "EMA2") (class "Default")
      (node (ref "IC19") (pin "12") (pinfunction "5Q_12") (pintype "tri_state"))
      (node (ref "IC38") (pin "2") (pinfunction "A12_2") (pintype "input"))
      (node (ref "IC39") (pin "2") (pinfunction "A12_2") (pintype "input"))
      (node (ref "SV1") (pin "30") (pinfunction "30_30") (pintype "passive"))
    )
    (net (code "46") (name "ERROR") (class "Default")
      (node (ref "IC10") (pin "6") (pinfunction "O_6") (pintype "output"))
      (node (ref "IC6") (pin "19") (pinfunction "G_19") (pintype "input"))
      (node (ref "IC9") (pin "19") (pinfunction "G_19") (pintype "input"))
    )
    (net (code "47") (name "FLD0") (class "Default")
      (node (ref "IC19") (pin "17") (pinfunction "7D_17") (pintype "input"))
      (node (ref "IC21") (pin "14") (pinfunction "Y3_14") (pintype "tri_state"))
      (node (ref "IC21") (pin "9") (pinfunction "Y1_9") (pintype "tri_state"))
      (node (ref "RN3") (pin "2") (pinfunction "2_2") (pintype "passive"))
    )
    (net (code "48") (name "FLD1") (class "Default")
      (node (ref "IC19") (pin "14") (pinfunction "6D_14") (pintype "input"))
      (node (ref "IC21") (pin "16") (pinfunction "Y2_16") (pintype "tri_state"))
      (node (ref "IC21") (pin "7") (pinfunction "Y2_7") (pintype "tri_state"))
      (node (ref "RN3") (pin "3") (pinfunction "3_3") (pintype "passive"))
    )
    (net (code "49") (name "FLD2") (class "Default")
      (node (ref "IC19") (pin "13") (pinfunction "5D_13") (pintype "input"))
      (node (ref "IC21") (pin "18") (pinfunction "Y1_18") (pintype "tri_state"))
      (node (ref "IC21") (pin "5") (pinfunction "Y3_5") (pintype "tri_state"))
      (node (ref "RN3") (pin "4") (pinfunction "4_4") (pintype "passive"))
    )
    (net (code "50") (name "GND") (class "Default")
      (node (ref "CPU") (pin "15") (pinfunction "OSCIN_15") (pintype "input"))
      (node (ref "IC11") (pin "2") (pinfunction "D_2") (pintype "input"))
      (node (ref "IC18") (pin "12") (pinfunction "D_12") (pintype "input"))
      (node (ref "IC18") (pin "2") (pinfunction "D_2") (pintype "input"))
      (node (ref "IC19") (pin "1") (pinfunction "OC_1") (pintype "input"))
      (node (ref "IC19") (pin "18") (pinfunction "8D_18") (pintype "input"))
      (node (ref "IC21") (pin "17") (pinfunction "A4_17") (pintype "input"))
      (node (ref "IC21") (pin "8") (pinfunction "A4_8") (pintype "input"))
      (node (ref "IC24") (pin "1") (pinfunction "M_1") (pintype "input"))
      (node (ref "IC24") (pin "10") (pinfunction "G2_10") (pintype "input"))
      (node (ref "IC24") (pin "11") (pinfunction "D4_11") (pintype "input"))
      (node (ref "IC24") (pin "2") (pinfunction "N_2") (pintype "input"))
      (node (ref "IC24") (pin "9") (pinfunction "G1_9") (pintype "input"))
      (node (ref "IC25") (pin "1") (pinfunction "M_1") (pintype "input"))
      (node (ref "IC25") (pin "10") (pinfunction "G2_10") (pintype "input"))
      (node (ref "IC25") (pin "11") (pinfunction "D4_11") (pintype "input"))
      (node (ref "IC25") (pin "2") (pinfunction "N_2") (pintype "input"))
      (node (ref "IC25") (pin "9") (pinfunction "G1_9") (pintype "input"))
      (node (ref "IC27") (pin "9") (pinfunction "A8_9") (pintype "bidirectional"))
      (node (ref "IC28") (pin "1") (pinfunction "M_1") (pintype "input"))
      (node (ref "IC28") (pin "10") (pinfunction "G2_10") (pintype "input"))
      (node (ref "IC28") (pin "11") (pinfunction "D4_11") (pintype "input"))
      (node (ref "IC28") (pin "2") (pinfunction "N_2") (pintype "input"))
      (node (ref "IC28") (pin "9") (pinfunction "G1_9") (pintype "input"))
      (node (ref "IC30") (pin "4") (pinfunction "A3_4") (pintype "bidirectional"))
      (node (ref "IC30") (pin "5") (pinfunction "A4_5") (pintype "bidirectional"))
      (node (ref "IC30") (pin "6") (pinfunction "A5_6") (pintype "bidirectional"))
      (node (ref "IC30") (pin "7") (pinfunction "A6_7") (pintype "bidirectional"))
      (node (ref "IC30") (pin "8") (pinfunction "A7_8") (pintype "bidirectional"))
      (node (ref "IC30") (pin "9") (pinfunction "A8_9") (pintype "bidirectional"))
      (node (ref "IC32") (pin "2") (pinfunction "A1_2") (pintype "bidirectional"))
      (node (ref "IC32") (pin "3") (pinfunction "A2_3") (pintype "bidirectional"))
      (node (ref "IC32") (pin "4") (pinfunction "A3_4") (pintype "bidirectional"))
      (node (ref "IC32") (pin "8") (pinfunction "A7_8") (pintype "bidirectional"))
      (node (ref "IC32") (pin "9") (pinfunction "A8_9") (pintype "bidirectional"))
      (node (ref "IC33") (pin "2") (pinfunction "A1_2") (pintype "bidirectional"))
      (node (ref "IC33") (pin "3") (pinfunction "A2_3") (pintype "bidirectional"))
      (node (ref "IC33") (pin "4") (pinfunction "A3_4") (pintype "bidirectional"))
      (node (ref "IC33") (pin "5") (pinfunction "A4_5") (pintype "bidirectional"))
      (node (ref "IC33") (pin "6") (pinfunction "A5_6") (pintype "bidirectional"))
      (node (ref "IC33") (pin "7") (pinfunction "A6_7") (pintype "bidirectional"))
      (node (ref "IC33") (pin "8") (pinfunction "A7_8") (pintype "bidirectional"))
      (node (ref "IC33") (pin "9") (pinfunction "A8_9") (pintype "bidirectional"))
      (node (ref "IC34") (pin "13") (pinfunction "4B_13") (pintype "input"))
      (node (ref "IC34") (pin "14") (pinfunction "4A_14") (pintype "input"))
      (node (ref "IC34") (pin "15") (pinfunction "G_15") (pintype "input"))
      (node (ref "IC37") (pin "9") (pinfunction "A8_9") (pintype "bidirectional"))
      (node (ref "IC38") (pin "14") (pinfunction "VSS_14") (pintype "power_in"))
      (node (ref "IC39") (pin "14") (pinfunction "VSS_14") (pintype "power_in"))
      (node (ref "IC41") (pin "7") (pinfunction "G_7") (pintype "input"))
      (node (ref "IC42") (pin "18") (pinfunction "D8_18") (pintype "input"))
      (node (ref "IC46") (pin "8") (pinfunction "A4_8") (pintype "input"))
      (node (ref "IC47") (pin "8") (pinfunction "A4_8") (pintype "input"))
      (node (ref "IC48") (pin "8") (pinfunction "A4_8") (pintype "input"))
      (node (ref "IC5") (pin "1") (pinfunction "OC_1") (pintype "input"))
      (node (ref "IC7") (pin "4") (pinfunction "G2A_4") (pintype "input"))
      (node (ref "IC7") (pin "5") (pinfunction "G2B_5") (pintype "input"))
      (node (ref "QG1") (pin "4") (pinfunction "GND_4") (pintype "power_in"))
      (node (ref "QG2") (pin "7") (pinfunction "GND_7") (pintype "power_in"))
      (node (ref "RN1") (pin "1") (pinfunction "1_1") (pintype "passive"))
      (node (ref "RN3") (pin "1") (pinfunction "1_1") (pintype "passive"))
      (node (ref "SV1") (pin "37") (pinfunction "37_37") (pintype "passive"))
      (node (ref "SV1") (pin "39") (pinfunction "39_39") (pintype "passive"))
    )
    (net (code "51") (name "IFETCH") (class "Default")
      (node (ref "CPU") (pin "36") (pinfunction "IFETCH_36") (pintype "output"))
      (node (ref "IC10") (pin "12") (pinfunction "I0_12") (pintype "input"))
      (node (ref "IC15") (pin "4") (pinfunction "I0_4") (pintype "input"))
      (node (ref "IC15") (pin "9") (pinfunction "I0_9") (pintype "input"))
      (node (ref "IC22") (pin "4") (pinfunction "I2_4") (pintype "input"))
    )
    (net (code "52") (name "IFLD0") (class "Default")
      (node (ref "IC21") (pin "6") (pinfunction "A3_6") (pintype "input"))
      (node (ref "IC24") (pin "5") (pinfunction "Q3_5") (pintype "tri_state"))
      (node (ref "IC27") (pin "7") (pinfunction "A6_7") (pintype "bidirectional"))
      (node (ref "IC34") (pin "11") (pinfunction "3A_11") (pintype "input"))
      (node (ref "IC42") (pin "14") (pinfunction "D6_14") (pintype "input"))
    )
    (net (code "53") (name "IFLD1") (class "Default")
      (node (ref "IC21") (pin "4") (pinfunction "A2_4") (pintype "input"))
      (node (ref "IC24") (pin "4") (pinfunction "Q2_4") (pintype "tri_state"))
      (node (ref "IC27") (pin "6") (pinfunction "A5_6") (pintype "bidirectional"))
      (node (ref "IC34") (pin "5") (pinfunction "2A_5") (pintype "input"))
      (node (ref "IC42") (pin "13") (pinfunction "D5_13") (pintype "input"))
    )
    (net (code "54") (name "IFLD2") (class "Default")
      (node (ref "IC21") (pin "2") (pinfunction "A1_2") (pintype "input"))
      (node (ref "IC24") (pin "3") (pinfunction "Q1_3") (pintype "tri_state"))
      (node (ref "IC27") (pin "5") (pinfunction "A4_5") (pintype "bidirectional"))
      (node (ref "IC34") (pin "2") (pinfunction "1A_2") (pintype "input"))
      (node (ref "IC42") (pin "8") (pinfunction "D4_8") (pintype "input"))
    )
    (net (code "55") (name "INHIBIT") (class "Default")
      (node (ref "IC15") (pin "13") (pinfunction "I1_13") (pintype "input"))
      (node (ref "IC16") (pin "2") (pinfunction "I1_2") (pintype "input"))
      (node (ref "IC18") (pin "5") (pinfunction "Q_5") (pintype "output"))
      (node (ref "IC30") (pin "2") (pinfunction "A1_2") (pintype "bidirectional"))
    )
    (net (code "56") (name "INTGNT") (class "Default")
      (node (ref "CPU") (pin "39") (pinfunction "INTGNT_39") (pintype "output"))
      (node (ref "IC26") (pin "1") (pinfunction "I0_1") (pintype "input"))
      (node (ref "IC42") (pin "11") (pinfunction "CLK_11") (pintype "input"))
      (node (ref "SV1") (pin "6") (pinfunction "6_6") (pintype "passive"))
    )
    (net (code "57") (name "IR0") (class "Default")
      (node (ref "IC3") (pin "9") (pinfunction "Q4_9") (pintype "output"))
      (node (ref "IC7") (pin "3") (pinfunction "C_3") (pintype "input"))
    )
    (net (code "58") (name "IR1") (class "Default")
      (node (ref "IC3") (pin "10") (pinfunction "Q3_10") (pintype "output"))
      (node (ref "IC7") (pin "2") (pinfunction "B_2") (pintype "input"))
    )
    (net (code "59") (name "IR2") (class "Default")
      (node (ref "IC3") (pin "15") (pinfunction "Q2_15") (pintype "output"))
      (node (ref "IC7") (pin "1") (pinfunction "A_1") (pintype "input"))
    )
    (net (code "60") (name "IR3") (class "Default")
      (node (ref "IC3") (pin "16") (pinfunction "Q1_16") (pintype "output"))
      (node (ref "IC4") (pin "6") (pinfunction "G1_6") (pintype "input"))
    )
    (net (code "61") (name "IR4") (class "Default")
      (node (ref "IC2") (pin "9") (pinfunction "Q4_9") (pintype "output"))
      (node (ref "IC8") (pin "12") (pinfunction "I2_12") (pintype "input"))
    )
    (net (code "62") (name "IR6") (class "Default")
      (node (ref "IC14") (pin "3") (pinfunction "C_3") (pintype "input"))
      (node (ref "IC2") (pin "15") (pinfunction "Q2_15") (pintype "output"))
      (node (ref "IC47") (pin "15") (pinfunction "A3_15") (pintype "input"))
      (node (ref "IC47") (pin "6") (pinfunction "A3_6") (pintype "input"))
    )
    (net (code "63") (name "IR7") (class "Default")
      (node (ref "IC14") (pin "2") (pinfunction "B_2") (pintype "input"))
      (node (ref "IC2") (pin "16") (pinfunction "Q1_16") (pintype "output"))
      (node (ref "IC47") (pin "13") (pinfunction "A2_13") (pintype "input"))
      (node (ref "IC47") (pin "4") (pinfunction "A2_4") (pintype "input"))
    )
    (net (code "64") (name "IR8") (class "Default")
      (node (ref "IC1") (pin "9") (pinfunction "Q4_9") (pintype "output"))
      (node (ref "IC14") (pin "1") (pinfunction "A_1") (pintype "input"))
      (node (ref "IC47") (pin "11") (pinfunction "A1_11") (pintype "input"))
      (node (ref "IC47") (pin "2") (pinfunction "A1_2") (pintype "input"))
    )
    (net (code "65") (name "IR9") (class "Default")
      (node (ref "IC1") (pin "10") (pinfunction "Q3_10") (pintype "output"))
      (node (ref "IC13") (pin "3") (pinfunction "C_3") (pintype "input"))
      (node (ref "IC14") (pin "6") (pinfunction "G1_6") (pintype "input"))
      (node (ref "IC17") (pin "2") (pinfunction "I1_2") (pintype "input"))
      (node (ref "IC4") (pin "3") (pinfunction "C_3") (pintype "input"))
    )
    (net (code "66") (name "IR10") (class "Default")
      (node (ref "IC1") (pin "15") (pinfunction "Q2_15") (pintype "output"))
      (node (ref "IC13") (pin "2") (pinfunction "B_2") (pintype "input"))
      (node (ref "IC4") (pin "2") (pinfunction "B_2") (pintype "input"))
    )
    (net (code "67") (name "IR11") (class "Default")
      (node (ref "IC1") (pin "16") (pinfunction "Q1_16") (pintype "output"))
      (node (ref "IC13") (pin "1") (pinfunction "A_1") (pintype "input"))
      (node (ref "IC4") (pin "1") (pinfunction "A_1") (pintype "input"))
    )
    (net (code "68") (name "JMPDONE") (class "Default")
      (node (ref "IC15") (pin "12") (pinfunction "I0_12") (pintype "input"))
      (node (ref "IC15") (pin "8") (pinfunction "O_8") (pintype "output"))
      (node (ref "IC18") (pin "3") (pinfunction "CLK_3") (pintype "input"))
      (node (ref "IC24") (pin "7") (pinfunction "CLK_7") (pintype "input"))
      (node (ref "IC31") (pin "11") (pinfunction "CLK_11") (pintype "input"))
    )
    (net (code "69") (name "JMP_OR_JMS") (class "Default")
      (node (ref "IC10") (pin "8") (pinfunction "O_8") (pintype "output"))
      (node (ref "IC15") (pin "10") (pinfunction "I1_10") (pintype "input"))
    )
    (net (code "70") (name "LINK") (class "Default")
      (node (ref "CPU") (pin "29") (pinfunction "LINK_29") (pintype "output"))
      (node (ref "PAD5") (pin "1") (pinfunction "P_1") (pintype "passive"))
    )
    (net (code "71") (name "LXMAR") (class "Default")
      (node (ref "CPU") (pin "10") (pinfunction "LXMAR_10") (pintype "output"))
      (node (ref "IC19") (pin "11") (pinfunction "ENC_11") (pintype "input"))
      (node (ref "IC26") (pin "2") (pinfunction "I1_2") (pintype "input"))
      (node (ref "IC5") (pin "11") (pinfunction "ENC_11") (pintype "input"))
      (node (ref "SV1") (pin "28") (pinfunction "28_28") (pintype "passive"))
    )
    (net (code "72") (name "MA0") (class "Default")
      (node (ref "IC19") (pin "9") (pinfunction "4Q_9") (pintype "tri_state"))
      (node (ref "IC38") (pin "23") (pinfunction "A11_23") (pintype "input"))
      (node (ref "IC39") (pin "23") (pinfunction "A11_23") (pintype "input"))
    )
    (net (code "73") (name "MA1") (class "Default")
      (node (ref "IC19") (pin "6") (pinfunction "3Q_6") (pintype "tri_state"))
      (node (ref "IC38") (pin "21") (pinfunction "A10_21") (pintype "input"))
      (node (ref "IC39") (pin "21") (pinfunction "A10_21") (pintype "input"))
    )
    (net (code "74") (name "MA2") (class "Default")
      (node (ref "IC19") (pin "5") (pinfunction "2Q_5") (pintype "tri_state"))
      (node (ref "IC38") (pin "24") (pinfunction "A9_24") (pintype "input"))
      (node (ref "IC39") (pin "24") (pinfunction "A9_24") (pintype "input"))
    )
    (net (code "75") (name "MA3") (class "Default")
      (node (ref "IC19") (pin "2") (pinfunction "1Q_2") (pintype "tri_state"))
      (node (ref "IC38") (pin "25") (pinfunction "A8_25") (pintype "input"))
      (node (ref "IC39") (pin "25") (pinfunction "A8_25") (pintype "input"))
    )
    (net (code "76") (name "MA4") (class "Default")
      (node (ref "IC38") (pin "3") (pinfunction "A7_3") (pintype "input"))
      (node (ref "IC39") (pin "3") (pinfunction "A7_3") (pintype "input"))
      (node (ref "IC5") (pin "19") (pinfunction "8Q_19") (pintype "tri_state"))
    )
    (net (code "77") (name "MA5") (class "Default")
      (node (ref "IC38") (pin "4") (pinfunction "A6_4") (pintype "input"))
      (node (ref "IC39") (pin "4") (pinfunction "A6_4") (pintype "input"))
      (node (ref "IC5") (pin "16") (pinfunction "7Q_16") (pintype "tri_state"))
    )
    (net (code "78") (name "MA6") (class "Default")
      (node (ref "IC38") (pin "5") (pinfunction "A5_5") (pintype "input"))
      (node (ref "IC39") (pin "5") (pinfunction "A5_5") (pintype "input"))
      (node (ref "IC5") (pin "15") (pinfunction "6Q_15") (pintype "tri_state"))
    )
    (net (code "79") (name "MA7") (class "Default")
      (node (ref "IC38") (pin "6") (pinfunction "A4_6") (pintype "input"))
      (node (ref "IC39") (pin "6") (pinfunction "A4_6") (pintype "input"))
      (node (ref "IC5") (pin "12") (pinfunction "5Q_12") (pintype "tri_state"))
    )
    (net (code "80") (name "MA8") (class "Default")
      (node (ref "IC38") (pin "7") (pinfunction "A3_7") (pintype "input"))
      (node (ref "IC39") (pin "7") (pinfunction "A3_7") (pintype "input"))
      (node (ref "IC5") (pin "9") (pinfunction "4Q_9") (pintype "tri_state"))
    )
    (net (code "81") (name "MA9") (class "Default")
      (node (ref "IC38") (pin "8") (pinfunction "A2_8") (pintype "input"))
      (node (ref "IC39") (pin "8") (pinfunction "A2_8") (pintype "input"))
      (node (ref "IC5") (pin "6") (pinfunction "3Q_6") (pintype "tri_state"))
    )
    (net (code "82") (name "MA10") (class "Default")
      (node (ref "IC38") (pin "9") (pinfunction "A1_9") (pintype "input"))
      (node (ref "IC39") (pin "9") (pinfunction "A1_9") (pintype "input"))
      (node (ref "IC5") (pin "5") (pinfunction "2Q_5") (pintype "tri_state"))
    )
    (net (code "83") (name "MA11") (class "Default")
      (node (ref "IC38") (pin "10") (pinfunction "A0_10") (pintype "input"))
      (node (ref "IC39") (pin "10") (pinfunction "A0_10") (pintype "input"))
      (node (ref "IC5") (pin "2") (pinfunction "1Q_2") (pintype "tri_state"))
    )
    (net (code "84") (name "Net-(CPUA-OSCOUT)") (class "Default")
      (node (ref "CPU") (pin "14") (pinfunction "OSCOUT_14") (pintype "output"))
      (node (ref "QG1") (pin "5") (pinfunction "OUT_5") (pintype "output"))
      (node (ref "QG2") (pin "8") (pinfunction "OUT_8") (pintype "output"))
    )
    (net (code "85") (name "Net-(IC10D-O)") (class "Default")
      (node (ref "IC10") (pin "11") (pinfunction "O_11") (pintype "output"))
      (node (ref "IC20") (pin "3") (pinfunction "CLK_3") (pintype "input"))
    )
    (net (code "86") (name "Net-(IC11B-CLR)") (class "Default")
      (node (ref "IC11") (pin "13") (pinfunction "CLR_13") (pintype "input"))
      (node (ref "IC31") (pin "13") (pinfunction "CLR_13") (pintype "input"))
      (node (ref "IC40") (pin "12") (pinfunction "O_12") (pintype "output"))
    )
    (net (code "87") (name "Net-(IC11B-D)") (class "Default")
      (node (ref "IC11") (pin "12") (pinfunction "D_12") (pintype "input"))
      (node (ref "IC41") (pin "5") (pinfunction "Y_5") (pintype "output"))
    )
    (net (code "88") (name "Net-(IC15A-O)") (class "Default")
      (node (ref "IC15") (pin "3") (pinfunction "O_3") (pintype "output"))
      (node (ref "IC3") (pin "7") (pinfunction "D4_7") (pintype "input"))
    )
    (net (code "89") (name "Net-(IC15B-O)") (class "Default")
      (node (ref "IC1") (pin "13") (pinfunction "C12_13") (pintype "input"))
      (node (ref "IC1") (pin "4") (pinfunction "C34_4") (pintype "input"))
      (node (ref "IC15") (pin "6") (pinfunction "O_6") (pintype "output"))
      (node (ref "IC2") (pin "13") (pinfunction "C12_13") (pintype "input"))
      (node (ref "IC2") (pin "4") (pinfunction "C34_4") (pintype "input"))
      (node (ref "IC3") (pin "13") (pinfunction "C12_13") (pintype "input"))
      (node (ref "IC3") (pin "4") (pinfunction "C34_4") (pintype "input"))
    )
    (net (code "90") (name "Net-(IC15D-O)") (class "Default")
      (node (ref "IC15") (pin "11") (pinfunction "O_11") (pintype "output"))
      (node (ref "IC18") (pin "11") (pinfunction "CLK_11") (pintype "input"))
    )
    (net (code "91") (name "Net-(IC16B-O)") (class "Default")
      (node (ref "IC16") (pin "6") (pinfunction "O_6") (pintype "output"))
      (node (ref "IC21") (pin "1") (pinfunction "G_1") (pintype "input"))
    )
    (net (code "92") (name "Net-(IC16C-O)") (class "Default")
      (node (ref "IC16") (pin "8") (pinfunction "O_8") (pintype "output"))
      (node (ref "IC29") (pin "13") (pinfunction "I_13") (pintype "input"))
    )
    (net (code "93") (name "Net-(IC17A-O)") (class "Default")
      (node (ref "IC17") (pin "3") (pinfunction "O_3") (pintype "output"))
      (node (ref "IC17") (pin "4") (pinfunction "I0_4") (pintype "input"))
      (node (ref "IC17") (pin "9") (pinfunction "I0_9") (pintype "input"))
    )
    (net (code "94") (name "Net-(IC18A-PRE)") (class "Default")
      (node (ref "IC18") (pin "4") (pinfunction "PRE_4") (pintype "input"))
      (node (ref "IC23") (pin "6") (pinfunction "O_6") (pintype "output"))
    )
    (net (code "95") (name "Net-(IC22B-O)") (class "Default")
      (node (ref "IC22") (pin "8") (pinfunction "O_8") (pintype "output"))
      (node (ref "IC23") (pin "4") (pinfunction "I0_4") (pintype "input"))
      (node (ref "IC23") (pin "5") (pinfunction "I1_5") (pintype "input"))
    )
    (net (code "96") (name "Net-(IC24A-CLR)") (class "Default")
      (node (ref "IC24") (pin "15") (pinfunction "CLR_15") (pintype "input"))
      (node (ref "IC25") (pin "15") (pinfunction "CLR_15") (pintype "input"))
      (node (ref "IC26") (pin "6") (pinfunction "O_6") (pintype "output"))
      (node (ref "IC28") (pin "15") (pinfunction "CLR_15") (pintype "input"))
    )
    (net (code "97") (name "Net-(IC27A-G)") (class "Default")
      (node (ref "IC27") (pin "19") (pinfunction "G_19") (pintype "input"))
      (node (ref "IC30") (pin "19") (pinfunction "G_19") (pintype "input"))
      (node (ref "IC35") (pin "6") (pinfunction "O_6") (pintype "output"))
    )
    (net (code "98") (name "Net-(IC29E-I)") (class "Default")
      (node (ref "IC29") (pin "11") (pinfunction "I_11") (pintype "input"))
      (node (ref "IC31") (pin "5") (pinfunction "Q_5") (pintype "output"))
    )
    (net (code "99") (name "Net-(IC31A-CLR)") (class "Default")
      (node (ref "IC31") (pin "1") (pinfunction "CLR_1") (pintype "input"))
      (node (ref "IC35") (pin "11") (pinfunction "O_11") (pintype "output"))
    )
    (net (code "100") (name "Net-(IC32A-A4)") (class "Default")
      (node (ref "IC32") (pin "5") (pinfunction "A4_5") (pintype "bidirectional"))
      (node (ref "IC34") (pin "4") (pinfunction "1Y_4") (pintype "output"))
    )
    (net (code "101") (name "Net-(IC32A-A5)") (class "Default")
      (node (ref "IC32") (pin "6") (pinfunction "A5_6") (pintype "bidirectional"))
      (node (ref "IC34") (pin "7") (pinfunction "2Y_7") (pintype "output"))
    )
    (net (code "102") (name "Net-(IC32A-A6)") (class "Default")
      (node (ref "IC32") (pin "7") (pinfunction "A6_7") (pintype "bidirectional"))
      (node (ref "IC34") (pin "9") (pinfunction "3Y_9") (pintype "output"))
    )
    (net (code "103") (name "Net-(IC32A-G)") (class "Default")
      (node (ref "IC32") (pin "19") (pinfunction "G_19") (pintype "input"))
      (node (ref "IC35") (pin "3") (pinfunction "O_3") (pintype "output"))
      (node (ref "IC36") (pin "5") (pinfunction "I1_5") (pintype "input"))
    )
    (net (code "104") (name "Net-(IC33A-G)") (class "Default")
      (node (ref "IC33") (pin "19") (pinfunction "G_19") (pintype "input"))
      (node (ref "IC36") (pin "6") (pinfunction "O_6") (pintype "output"))
    )
    (net (code "105") (name "Net-(IC35A-I0)") (class "Default")
      (node (ref "IC35") (pin "1") (pinfunction "I0_1") (pintype "input"))
      (node (ref "IC36") (pin "3") (pinfunction "O_3") (pintype "output"))
    )
    (net (code "106") (name "Net-(IC35C-O)") (class "Default")
      (node (ref "IC35") (pin "8") (pinfunction "O_8") (pintype "output"))
      (node (ref "IC36") (pin "4") (pinfunction "I0_4") (pintype "input"))
      (node (ref "IC37") (pin "19") (pinfunction "G_19") (pintype "input"))
    )
    (net (code "107") (name "Net-(QG1-TS)") (class "Default")
      (node (ref "QG1") (pin "1") (pinfunction "TS_1") (pintype "passive"))
      (node (ref "QG2") (pin "1") (pinfunction "TS_1") (pintype "passive"))
    )
    (net (code "108") (name "POPR") (class "Default")
      (node (ref "IC10") (pin "2") (pinfunction "I1_2") (pintype "input"))
      (node (ref "IC8") (pin "6") (pinfunction "O_6") (pintype "output"))
    )
    (net (code "109") (name "RUN") (class "Default")
      (node (ref "CPU") (pin "2") (pinfunction "RUN_2") (pintype "output"))
      (node (ref "PAD6") (pin "1") (pinfunction "P_1") (pintype "passive"))
    )
    (net (code "110") (name "SF0") (class "Default")
      (node (ref "IC37") (pin "8") (pinfunction "A7_8") (pintype "bidirectional"))
      (node (ref "IC41") (pin "14") (pinfunction "D5_14") (pintype "input"))
      (node (ref "IC42") (pin "16") (pinfunction "Q7_16") (pintype "output"))
    )
    (net (code "111") (name "SF1") (class "Default")
      (node (ref "IC37") (pin "7") (pinfunction "A6_7") (pintype "bidirectional"))
      (node (ref "IC42") (pin "15") (pinfunction "Q6_15") (pintype "output"))
      (node (ref "IC48") (pin "6") (pinfunction "A3_6") (pintype "input"))
    )
    (net (code "112") (name "SF2") (class "Default")
      (node (ref "IC37") (pin "6") (pinfunction "A5_6") (pintype "bidirectional"))
      (node (ref "IC42") (pin "12") (pinfunction "Q5_12") (pintype "output"))
      (node (ref "IC48") (pin "4") (pinfunction "A2_4") (pintype "input"))
    )
    (net (code "113") (name "SF3") (class "Default")
      (node (ref "IC37") (pin "5") (pinfunction "A4_5") (pintype "bidirectional"))
      (node (ref "IC42") (pin "9") (pinfunction "Q4_9") (pintype "output"))
      (node (ref "IC48") (pin "2") (pinfunction "A1_2") (pintype "input"))
    )
    (net (code "114") (name "SF4") (class "Default")
      (node (ref "IC37") (pin "4") (pinfunction "A3_4") (pintype "bidirectional"))
      (node (ref "IC42") (pin "6") (pinfunction "Q3_6") (pintype "output"))
      (node (ref "IC48") (pin "15") (pinfunction "A3_15") (pintype "input"))
    )
    (net (code "115") (name "SF5") (class "Default")
      (node (ref "IC37") (pin "3") (pinfunction "A2_3") (pintype "bidirectional"))
      (node (ref "IC42") (pin "5") (pinfunction "Q2_5") (pintype "output"))
      (node (ref "IC48") (pin "13") (pinfunction "A2_13") (pintype "input"))
    )
    (net (code "116") (name "SF6") (class "Default")
      (node (ref "IC37") (pin "2") (pinfunction "A1_2") (pintype "bidirectional"))
      (node (ref "IC42") (pin "2") (pinfunction "Q1_2") (pintype "output"))
      (node (ref "IC48") (pin "11") (pinfunction "A1_11") (pintype "input"))
    )
    (net (code "117") (name "UB") (class "Default")
      (node (ref "IC11") (pin "9") (pinfunction "Q_9") (pintype "output"))
      (node (ref "IC31") (pin "12") (pinfunction "D_12") (pintype "input"))
      (node (ref "IC41") (pin "1") (pinfunction "D3_1") (pintype "input"))
      (node (ref "IC41") (pin "12") (pinfunction "D7_12") (pintype "input"))
      (node (ref "IC41") (pin "15") (pinfunction "D4_15") (pintype "input"))
      (node (ref "IC41") (pin "2") (pinfunction "D2_2") (pintype "input"))
      (node (ref "IC41") (pin "3") (pinfunction "D1_3") (pintype "input"))
      (node (ref "IC41") (pin "4") (pinfunction "D0_4") (pintype "input"))
    )
    (net (code "118") (name "USER_MODE") (class "Default")
      (node (ref "IC10") (pin "1") (pinfunction "I0_1") (pintype "input"))
      (node (ref "IC27") (pin "8") (pinfunction "A7_8") (pintype "bidirectional"))
      (node (ref "IC31") (pin "9") (pinfunction "Q_9") (pintype "output"))
      (node (ref "IC42") (pin "17") (pinfunction "D7_17") (pintype "input"))
    )
    (net (code "119") (name "VCC") (class "Default")
      (node (ref "IC12") (pin "1") (pinfunction "I0_1") (pintype "input"))
      (node (ref "IC12") (pin "2") (pinfunction "I1_2") (pintype "input"))
      (node (ref "IC13") (pin "6") (pinfunction "G1_6") (pintype "input"))
      (node (ref "IC17") (pin "12") (pinfunction "I0_12") (pintype "input"))
      (node (ref "IC17") (pin "13") (pinfunction "I1_13") (pintype "input"))
      (node (ref "IC20") (pin "10") (pinfunction "PRE_10") (pintype "input"))
      (node (ref "IC20") (pin "11") (pinfunction "CLK_11") (pintype "input"))
      (node (ref "IC20") (pin "12") (pinfunction "D_12") (pintype "input"))
      (node (ref "IC20") (pin "13") (pinfunction "CLR_13") (pintype "input"))
      (node (ref "IC20") (pin "2") (pinfunction "D_2") (pintype "input"))
      (node (ref "IC20") (pin "4") (pinfunction "PRE_4") (pintype "input"))
      (node (ref "IC22") (pin "1") (pinfunction "I0_1") (pintype "input"))
      (node (ref "IC23") (pin "12") (pinfunction "I0_12") (pintype "input"))
      (node (ref "IC23") (pin "13") (pinfunction "I1_13") (pintype "input"))
      (node (ref "IC27") (pin "1") (pinfunction "DIR_1") (pintype "input"))
      (node (ref "IC30") (pin "1") (pinfunction "DIR_1") (pintype "input"))
      (node (ref "IC31") (pin "10") (pinfunction "PRE_10") (pintype "input"))
      (node (ref "IC31") (pin "2") (pinfunction "D_2") (pintype "input"))
      (node (ref "IC31") (pin "4") (pinfunction "PRE_4") (pintype "input"))
      (node (ref "IC32") (pin "1") (pinfunction "DIR_1") (pintype "input"))
      (node (ref "IC33") (pin "1") (pinfunction "DIR_1") (pintype "input"))
      (node (ref "IC37") (pin "1") (pinfunction "DIR_1") (pintype "input"))
      (node (ref "IC38") (pin "28") (pinfunction "VCC_28") (pintype "power_in"))
      (node (ref "IC39") (pin "28") (pinfunction "VCC_28") (pintype "power_in"))
      (node (ref "IC7") (pin "6") (pinfunction "G1_6") (pintype "input"))
      (node (ref "IC8") (pin "9") (pinfunction "I0_9") (pintype "input"))
      (node (ref "QG1") (pin "8") (pinfunction "VCC_8") (pintype "power_in"))
      (node (ref "QG2") (pin "14") (pinfunction "VCC_14") (pintype "power_in"))
      (node (ref "RN4") (pin "1") (pinfunction "1_1") (pintype "passive"))
      (node (ref "SV1") (pin "1") (pinfunction "1_1") (pintype "passive"))
      (node (ref "SV1") (pin "3") (pinfunction "3_3") (pintype "passive"))
    )
    (net (code "120") (name "WASMEM") (class "Default")
      (node (ref "IC20") (pin "5") (pinfunction "Q_5") (pintype "output"))
      (node (ref "IC22") (pin "2") (pinfunction "I1_2") (pintype "input"))
    )
    (net (code "121") (name "XTA") (class "Default")
      (node (ref "CPU") (pin "9") (pinfunction "XTA_9") (pintype "output"))
      (node (ref "IC15") (pin "5") (pinfunction "I1_5") (pintype "input"))
      (node (ref "IC26") (pin "10") (pinfunction "I1_10") (pintype "input"))
      (node (ref "IC26") (pin "9") (pinfunction "I0_9") (pintype "input"))
      (node (ref "SV1") (pin "10") (pinfunction "10_10") (pintype "passive"))
    )
    (net (code "122") (name "XTB") (class "Default")
      (node (ref "CPU") (pin "12") (pinfunction "XTB_12") (pintype "output"))
      (node (ref "IC11") (pin "11") (pinfunction "CLK_11") (pintype "input"))
      (node (ref "IC26") (pin "12") (pinfunction "I0_12") (pintype "input"))
      (node (ref "IC26") (pin "13") (pinfunction "I1_13") (pintype "input"))
      (node (ref "IC41") (pin "9") (pinfunction "C_9") (pintype "input"))
      (node (ref "IC6") (pin "1") (pinfunction "DIR_1") (pintype "input"))
      (node (ref "IC9") (pin "1") (pinfunction "DIR_1") (pintype "input"))
      (node (ref "SV1") (pin "12") (pinfunction "12_12") (pintype "passive"))
    )
    (net (code "123") (name "XTC") (class "Default")
      (node (ref "CPU") (pin "13") (pinfunction "XTC_13") (pintype "output"))
      (node (ref "SV1") (pin "14") (pinfunction "14_14") (pintype "passive"))
    )
    (net (code "124") (name "ZF") (class "Default")
      (node (ref "IC16") (pin "5") (pinfunction "I1_5") (pintype "input"))
      (node (ref "IC18") (pin "9") (pinfunction "Q_9") (pintype "output"))
    )
    (net (code "125") (name "unconnected-(IC1A-~{Q3}-Pad11)") (class "Default")
      (node (ref "IC1") (pin "11") (pinfunction "~{Q3}_11") (pintype "output"))
    )
    (net (code "126") (name "unconnected-(IC2A-Q3-Pad10)") (class "Default")
      (node (ref "IC2") (pin "10") (pinfunction "Q3_10") (pintype "output"))
    )
    (net (code "127") (name "unconnected-(IC3A-~{Q2}-Pad14)") (class "Default")
      (node (ref "IC3") (pin "14") (pinfunction "~{Q2}_14") (pintype "output"))
    )
    (net (code "128") (name "unconnected-(IC3A-~{Q3}-Pad11)") (class "Default")
      (node (ref "IC3") (pin "11") (pinfunction "~{Q3}_11") (pintype "output"))
    )
    (net (code "129") (name "unconnected-(IC3A-~{Q4}-Pad8)") (class "Default")
      (node (ref "IC3") (pin "8") (pinfunction "~{Q4}_8") (pintype "output"))
    )
    (net (code "130") (name "unconnected-(IC4A-Y0-Pad15)") (class "Default")
      (node (ref "IC4") (pin "15") (pinfunction "Y0_15") (pintype "output"))
    )
    (net (code "131") (name "unconnected-(IC4A-Y1-Pad14)") (class "Default")
      (node (ref "IC4") (pin "14") (pinfunction "Y1_14") (pintype "output"))
    )
    (net (code "132") (name "unconnected-(IC4A-Y3-Pad12)") (class "Default")
      (node (ref "IC4") (pin "12") (pinfunction "Y3_12") (pintype "output"))
    )
    (net (code "133") (name "unconnected-(IC4A-Y5-Pad10)") (class "Default")
      (node (ref "IC4") (pin "10") (pinfunction "Y5_10") (pintype "output"))
    )
    (net (code "134") (name "unconnected-(IC4A-Y7-Pad7)") (class "Default")
      (node (ref "IC4") (pin "7") (pinfunction "Y7_7") (pintype "output"))
    )
    (net (code "135") (name "unconnected-(IC9A-A4-Pad5)") (class "Default")
      (node (ref "IC9") (pin "5") (pinfunction "A4_5") (pintype "bidirectional"))
    )
    (net (code "136") (name "unconnected-(IC9A-A5-Pad6)") (class "Default")
      (node (ref "IC9") (pin "6") (pinfunction "A5_6") (pintype "bidirectional"))
    )
    (net (code "137") (name "unconnected-(IC9A-A6-Pad7)") (class "Default")
      (node (ref "IC9") (pin "7") (pinfunction "A6_7") (pintype "bidirectional"))
    )
    (net (code "138") (name "unconnected-(IC9A-A7-Pad8)") (class "Default")
      (node (ref "IC9") (pin "8") (pinfunction "A7_8") (pintype "bidirectional"))
    )
    (net (code "139") (name "unconnected-(IC9A-B4-Pad15)") (class "Default")
      (node (ref "IC9") (pin "15") (pinfunction "B4_15") (pintype "bidirectional"))
    )
    (net (code "140") (name "unconnected-(IC9A-B5-Pad14)") (class "Default")
      (node (ref "IC9") (pin "14") (pinfunction "B5_14") (pintype "bidirectional"))
    )
    (net (code "141") (name "unconnected-(IC9A-B6-Pad13)") (class "Default")
      (node (ref "IC9") (pin "13") (pinfunction "B6_13") (pintype "bidirectional"))
    )
    (net (code "142") (name "unconnected-(IC9A-B7-Pad12)") (class "Default")
      (node (ref "IC9") (pin "12") (pinfunction "B7_12") (pintype "bidirectional"))
    )
    (net (code "143") (name "unconnected-(IC11A-Q-Pad5)") (class "Default")
      (node (ref "IC11") (pin "5") (pinfunction "Q_5") (pintype "output"))
    )
    (net (code "144") (name "unconnected-(IC11B-~{Q}-Pad8)") (class "Default")
      (node (ref "IC11") (pin "8") (pinfunction "~{Q}_8") (pintype "output"))
    )
    (net (code "145") (name "unconnected-(IC13A-Y0-Pad15)") (class "Default")
      (node (ref "IC13") (pin "15") (pinfunction "Y0_15") (pintype "output"))
    )
    (net (code "146") (name "unconnected-(IC13A-Y1-Pad14)") (class "Default")
      (node (ref "IC13") (pin "14") (pinfunction "Y1_14") (pintype "output"))
    )
    (net (code "147") (name "unconnected-(IC13A-Y2-Pad13)") (class "Default")
      (node (ref "IC13") (pin "13") (pinfunction "Y2_13") (pintype "output"))
    )
    (net (code "148") (name "unconnected-(IC13A-Y3-Pad12)") (class "Default")
      (node (ref "IC13") (pin "12") (pinfunction "Y3_12") (pintype "output"))
    )
    (net (code "149") (name "unconnected-(IC13A-Y6-Pad9)") (class "Default")
      (node (ref "IC13") (pin "9") (pinfunction "Y6_9") (pintype "output"))
    )
    (net (code "150") (name "unconnected-(IC17D-O-Pad11)") (class "Default")
      (node (ref "IC17") (pin "11") (pinfunction "O_11") (pintype "output"))
    )
    (net (code "151") (name "unconnected-(IC18A-~{Q}-Pad6)") (class "Default")
      (node (ref "IC18") (pin "6") (pinfunction "~{Q}_6") (pintype "output"))
    )
    (net (code "152") (name "unconnected-(IC18B-~{Q}-Pad8)") (class "Default")
      (node (ref "IC18") (pin "8") (pinfunction "~{Q}_8") (pintype "output"))
    )
    (net (code "153") (name "unconnected-(IC19A-8Q-Pad19)") (class "Default")
      (node (ref "IC19") (pin "19") (pinfunction "8Q_19") (pintype "tri_state"))
    )
    (net (code "154") (name "unconnected-(IC20A-~{Q}-Pad6)") (class "Default")
      (node (ref "IC20") (pin "6") (pinfunction "~{Q}_6") (pintype "output"))
    )
    (net (code "155") (name "unconnected-(IC20B-Q-Pad9)") (class "Default")
      (node (ref "IC20") (pin "9") (pinfunction "Q_9") (pintype "output"))
    )
    (net (code "156") (name "unconnected-(IC20B-~{Q}-Pad8)") (class "Default")
      (node (ref "IC20") (pin "8") (pinfunction "~{Q}_8") (pintype "output"))
    )
    (net (code "157") (name "unconnected-(IC21A-Y4-Pad12)") (class "Default")
      (node (ref "IC21") (pin "12") (pinfunction "Y4_12") (pintype "tri_state"))
    )
    (net (code "158") (name "unconnected-(IC21B-Y4-Pad3)") (class "Default")
      (node (ref "IC21") (pin "3") (pinfunction "Y4_3") (pintype "tri_state"))
    )
    (net (code "159") (name "unconnected-(IC23D-O-Pad11)") (class "Default")
      (node (ref "IC23") (pin "11") (pinfunction "O_11") (pintype "output"))
    )
    (net (code "160") (name "unconnected-(IC24A-Q4-Pad6)") (class "Default")
      (node (ref "IC24") (pin "6") (pinfunction "Q4_6") (pintype "tri_state"))
    )
    (net (code "161") (name "unconnected-(IC25A-Q4-Pad6)") (class "Default")
      (node (ref "IC25") (pin "6") (pinfunction "Q4_6") (pintype "tri_state"))
    )
    (net (code "162") (name "unconnected-(IC28A-Q4-Pad6)") (class "Default")
      (node (ref "IC28") (pin "6") (pinfunction "Q4_6") (pintype "tri_state"))
    )
    (net (code "163") (name "unconnected-(IC30A-B5-Pad14)") (class "Default")
      (node (ref "IC30") (pin "14") (pinfunction "B5_14") (pintype "bidirectional"))
    )
    (net (code "164") (name "unconnected-(IC30A-B6-Pad13)") (class "Default")
      (node (ref "IC30") (pin "13") (pinfunction "B6_13") (pintype "bidirectional"))
    )
    (net (code "165") (name "unconnected-(IC30A-B7-Pad12)") (class "Default")
      (node (ref "IC30") (pin "12") (pinfunction "B7_12") (pintype "bidirectional"))
    )
    (net (code "166") (name "unconnected-(IC30A-B8-Pad11)") (class "Default")
      (node (ref "IC30") (pin "11") (pinfunction "B8_11") (pintype "bidirectional"))
    )
    (net (code "167") (name "unconnected-(IC31A-~{Q}-Pad6)") (class "Default")
      (node (ref "IC31") (pin "6") (pinfunction "~{Q}_6") (pintype "output"))
    )
    (net (code "168") (name "unconnected-(IC31B-~{Q}-Pad8)") (class "Default")
      (node (ref "IC31") (pin "8") (pinfunction "~{Q}_8") (pintype "output"))
    )
    (net (code "169") (name "unconnected-(IC33A-B5-Pad14)") (class "Default")
      (node (ref "IC33") (pin "14") (pinfunction "B5_14") (pintype "bidirectional"))
    )
    (net (code "170") (name "unconnected-(IC33A-B6-Pad13)") (class "Default")
      (node (ref "IC33") (pin "13") (pinfunction "B6_13") (pintype "bidirectional"))
    )
    (net (code "171") (name "unconnected-(IC33A-B7-Pad12)") (class "Default")
      (node (ref "IC33") (pin "12") (pinfunction "B7_12") (pintype "bidirectional"))
    )
    (net (code "172") (name "unconnected-(IC33A-B8-Pad11)") (class "Default")
      (node (ref "IC33") (pin "11") (pinfunction "B8_11") (pintype "bidirectional"))
    )
    (net (code "173") (name "unconnected-(IC34A-4Y-Pad12)") (class "Default")
      (node (ref "IC34") (pin "12") (pinfunction "4Y_12") (pintype "output"))
    )
    (net (code "174") (name "unconnected-(IC39-I{slash}O4-Pad16)") (class "Default")
      (node (ref "IC39") (pin "16") (pinfunction "I/O4_16") (pintype "bidirectional"))
    )
    (net (code "175") (name "unconnected-(IC39-I{slash}O5-Pad17)") (class "Default")
      (node (ref "IC39") (pin "17") (pinfunction "I/O5_17") (pintype "bidirectional"))
    )
    (net (code "176") (name "unconnected-(IC39-I{slash}O6-Pad18)") (class "Default")
      (node (ref "IC39") (pin "18") (pinfunction "I/O6_18") (pintype "bidirectional"))
    )
    (net (code "177") (name "unconnected-(IC39-I{slash}O7-Pad19)") (class "Default")
      (node (ref "IC39") (pin "19") (pinfunction "I/O7_19") (pintype "bidirectional"))
    )
    (net (code "178") (name "unconnected-(IC41A-W-Pad6)") (class "Default")
      (node (ref "IC41") (pin "6") (pinfunction "W_6") (pintype "output"))
    )
    (net (code "179") (name "unconnected-(IC42A-Q8-Pad19)") (class "Default")
      (node (ref "IC42") (pin "19") (pinfunction "Q8_19") (pintype "output"))
    )
    (net (code "180") (name "unconnected-(IC46A-Y4-Pad12)") (class "Default")
      (node (ref "IC46") (pin "12") (pinfunction "Y4_12") (pintype "tri_state"))
    )
    (net (code "181") (name "unconnected-(IC46B-Y4-Pad3)") (class "Default")
      (node (ref "IC46") (pin "3") (pinfunction "Y4_3") (pintype "tri_state"))
    )
    (net (code "182") (name "unconnected-(IC47A-Y4-Pad12)") (class "Default")
      (node (ref "IC47") (pin "12") (pinfunction "Y4_12") (pintype "tri_state"))
    )
    (net (code "183") (name "unconnected-(IC47B-Y4-Pad3)") (class "Default")
      (node (ref "IC47") (pin "3") (pinfunction "Y4_3") (pintype "tri_state"))
    )
    (net (code "184") (name "unconnected-(IC48A-Y4-Pad12)") (class "Default")
      (node (ref "IC48") (pin "12") (pinfunction "Y4_12") (pintype "tri_state"))
    )
    (net (code "185") (name "unconnected-(IC48B-Y4-Pad3)") (class "Default")
      (node (ref "IC48") (pin "3") (pinfunction "Y4_3") (pintype "tri_state"))
    )
    (net (code "186") (name "unconnected-(SV1-Pad2)") (class "Default")
      (node (ref "SV1") (pin "2") (pinfunction "2_2") (pintype "passive"))
    )
    (net (code "187") (name "unconnected-(SV1-Pad4)") (class "Default")
      (node (ref "SV1") (pin "4") (pinfunction "4_4") (pintype "passive"))
    )
    (net (code "188") (name "unconnected-(SV1-Pad38)") (class "Default")
      (node (ref "SV1") (pin "38") (pinfunction "38_38") (pintype "passive"))
    )
    (net (code "189") (name "unconnected-(SV1-Pad40)") (class "Default")
      (node (ref "SV1") (pin "40") (pinfunction "40_40") (pintype "passive"))
    )
    (net (code "190") (name "~{00}") (class "Default")
      (node (ref "IC12") (pin "8") (pinfunction "O_8") (pintype "output"))
      (node (ref "IC13") (pin "4") (pinfunction "G2A_4") (pintype "input"))
    )
    (net (code "191") (name "~{2X}") (class "Default")
      (node (ref "IC14") (pin "4") (pinfunction "G2A_4") (pintype "input"))
      (node (ref "IC17") (pin "1") (pinfunction "I0_1") (pintype "input"))
      (node (ref "IC8") (pin "8") (pinfunction "O_8") (pintype "output"))
    )
    (net (code "192") (name "~{AND}") (class "Default")
      (node (ref "IC7") (pin "15") (pinfunction "Y0_15") (pintype "output"))
      (node (ref "PAD1") (pin "1") (pinfunction "P_1") (pintype "passive"))
    )
    (net (code "193") (name "~{C0}") (class "Default")
      (node (ref "CPU") (pin "32") (pinfunction "C0_32") (pintype "input"))
      (node (ref "RN4") (pin "7") (pinfunction "7_7") (pintype "passive"))
      (node (ref "SV1") (pin "18") (pinfunction "18_18") (pintype "passive"))
    )
    (net (code "194") (name "~{C1}") (class "Default")
      (node (ref "CPU") (pin "33") (pinfunction "C1_33") (pintype "input"))
      (node (ref "IC29") (pin "2") (pinfunction "O_2") (pintype "open_collector"))
      (node (ref "IC29") (pin "4") (pinfunction "O_4") (pintype "open_collector"))
      (node (ref "IC29") (pin "6") (pinfunction "O_6") (pintype "open_collector"))
      (node (ref "IC29") (pin "8") (pinfunction "O_8") (pintype "open_collector"))
      (node (ref "RN4") (pin "6") (pinfunction "6_6") (pintype "passive"))
      (node (ref "SV1") (pin "20") (pinfunction "20_20") (pintype "passive"))
    )
    (net (code "195") (name "~{C2}") (class "Default")
      (node (ref "CPU") (pin "34") (pinfunction "C2_34") (pintype "input"))
      (node (ref "RN4") (pin "5") (pinfunction "5_5") (pintype "passive"))
      (node (ref "SV1") (pin "22") (pinfunction "22_22") (pintype "passive"))
    )
    (net (code "196") (name "~{CAF}") (class "Default")
      (node (ref "IC13") (pin "7") (pinfunction "Y7_7") (pintype "output"))
      (node (ref "IC35") (pin "12") (pinfunction "I0_12") (pintype "input"))
    )
    (net (code "197") (name "~{CDF}") (class "Default")
      (node (ref "IC17") (pin "8") (pinfunction "O_8") (pintype "output"))
      (node (ref "IC40") (pin "10") (pinfunction "I1_10") (pintype "input"))
      (node (ref "IC47") (pin "17") (pinfunction "A4_17") (pintype "input"))
      (node (ref "IC47") (pin "19") (pinfunction "G_19") (pintype "input"))
    )
    (net (code "198") (name "~{CIF}") (class "Default")
      (node (ref "IC17") (pin "6") (pinfunction "O_6") (pintype "output"))
      (node (ref "IC22") (pin "10") (pinfunction "I1_10") (pintype "input"))
      (node (ref "IC40") (pin "4") (pinfunction "I1_4") (pintype "input"))
      (node (ref "IC47") (pin "1") (pinfunction "G_1") (pintype "input"))
    )
    (net (code "199") (name "~{CINT}") (class "Default")
      (node (ref "IC11") (pin "3") (pinfunction "CLK_3") (pintype "input"))
      (node (ref "IC14") (pin "15") (pinfunction "Y0_15") (pintype "output"))
    )
    (net (code "200") (name "~{CPREQ}") (class "Default")
      (node (ref "CPU") (pin "5") (pinfunction "CPREQ_5") (pintype "input"))
      (node (ref "SV1") (pin "36") (pinfunction "36_36") (pintype "passive"))
    )
    (net (code "201") (name "~{CPSEL}") (class "Default")
      (node (ref "CPU") (pin "38") (pinfunction "CPSEL_38") (pintype "output"))
      (node (ref "IC15") (pin "2") (pinfunction "I1_2") (pintype "input"))
      (node (ref "IC23") (pin "1") (pinfunction "I0_1") (pintype "input"))
      (node (ref "IC23") (pin "2") (pinfunction "I1_2") (pintype "input"))
    )
    (net (code "202") (name "~{CPUINTREQ}") (class "Default")
      (node (ref "CPU") (pin "8") (pinfunction "INTREQ_8") (pintype "input"))
      (node (ref "IC16") (pin "3") (pinfunction "O_3") (pintype "output"))
    )
    (net (code "203") (name "~{CUF}") (class "Default")
      (node (ref "IC14") (pin "9") (pinfunction "Y6_9") (pintype "output"))
      (node (ref "IC40") (pin "2") (pinfunction "I1_2") (pintype "input"))
    )
    (net (code "204") (name "~{DCA}") (class "Default")
      (node (ref "IC7") (pin "12") (pinfunction "Y3_12") (pintype "output"))
      (node (ref "PAD4") (pin "1") (pinfunction "P_1") (pintype "passive"))
    )
    (net (code "205") (name "~{DEVINTREQ}") (class "Default")
      (node (ref "IC16") (pin "1") (pinfunction "I0_1") (pintype "input"))
      (node (ref "IC23") (pin "10") (pinfunction "I1_10") (pintype "input"))
      (node (ref "IC23") (pin "9") (pinfunction "I0_9") (pintype "input"))
      (node (ref "SV1") (pin "8") (pinfunction "8_8") (pintype "passive"))
    )
    (net (code "206") (name "~{DEVSEL}") (class "Default")
      (node (ref "CPU") (pin "30") (pinfunction "DEVSEL_30") (pintype "output"))
      (node (ref "IC13") (pin "5") (pinfunction "G2B_5") (pintype "input"))
      (node (ref "IC14") (pin "5") (pinfunction "G2B_5") (pintype "input"))
      (node (ref "SV1") (pin "16") (pinfunction "16_16") (pintype "passive"))
    )
    (net (code "207") (name "~{DMAREQ}") (class "Default")
      (node (ref "CPU") (pin "4") (pinfunction "DMAREQ_4") (pintype "input"))
      (node (ref "SV1") (pin "7") (pinfunction "7_7") (pintype "passive"))
    )
    (net (code "208") (name "~{DORTF}") (class "Default")
      (node (ref "IC16") (pin "11") (pinfunction "O_11") (pintype "output"))
      (node (ref "IC40") (pin "3") (pinfunction "I0_3") (pintype "input"))
      (node (ref "IC40") (pin "9") (pinfunction "I0_9") (pintype "input"))
    )
    (net (code "209") (name "~{ERROR}") (class "Default")
      (node (ref "IC10") (pin "3") (pinfunction "O_3") (pintype "output"))
      (node (ref "IC10") (pin "4") (pinfunction "I0_4") (pintype "input"))
      (node (ref "IC10") (pin "5") (pinfunction "I1_5") (pintype "input"))
      (node (ref "IC11") (pin "4") (pinfunction "PRE_4") (pintype "input"))
    )
    (net (code "210") (name "~{GTF}") (class "Default")
      (node (ref "IC13") (pin "11") (pinfunction "Y4_11") (pintype "output"))
      (node (ref "IC29") (pin "1") (pinfunction "I_1") (pintype "input"))
      (node (ref "IC35") (pin "4") (pinfunction "I0_4") (pintype "input"))
    )
    (net (code "211") (name "~{HLT}") (class "Default")
      (node (ref "IC4") (pin "13") (pinfunction "Y2_13") (pintype "output"))
      (node (ref "IC8") (pin "1") (pinfunction "I0_1") (pintype "input"))
    )
    (net (code "212") (name "~{INTCLR}") (class "Default")
      (node (ref "IC26") (pin "3") (pinfunction "O_3") (pintype "output"))
      (node (ref "IC26") (pin "4") (pinfunction "I0_4") (pintype "input"))
      (node (ref "IC40") (pin "13") (pinfunction "I2_13") (pintype "input"))
    )
    (net (code "213") (name "~{IOT}") (class "Default")
      (node (ref "IC31") (pin "3") (pinfunction "CLK_3") (pintype "input"))
      (node (ref "IC7") (pin "9") (pinfunction "Y6_9") (pintype "output"))
      (node (ref "IC8") (pin "5") (pinfunction "I3_5") (pintype "input"))
    )
    (net (code "214") (name "~{IO_RESET}") (class "Default")
      (node (ref "IC29") (pin "10") (pinfunction "O_10") (pintype "open_collector"))
      (node (ref "SV1") (pin "11") (pinfunction "11_11") (pintype "passive"))
    )
    (net (code "215") (name "~{IR3}") (class "Default")
      (node (ref "IC12") (pin "12") (pinfunction "I7_12") (pintype "input"))
      (node (ref "IC3") (pin "1") (pinfunction "~{Q1}_1") (pintype "output"))
      (node (ref "IC8") (pin "13") (pinfunction "I3_13") (pintype "input"))
    )
    (net (code "216") (name "~{IR4}") (class "Default")
      (node (ref "IC12") (pin "11") (pinfunction "I6_11") (pintype "input"))
      (node (ref "IC2") (pin "8") (pinfunction "~{Q4}_8") (pintype "output"))
    )
    (net (code "217") (name "~{IR5}") (class "Default")
      (node (ref "IC12") (pin "6") (pinfunction "I5_6") (pintype "input"))
      (node (ref "IC2") (pin "11") (pinfunction "~{Q3}_11") (pintype "output"))
      (node (ref "IC8") (pin "10") (pinfunction "I1_10") (pintype "input"))
    )
    (net (code "218") (name "~{IR6}") (class "Default")
      (node (ref "IC12") (pin "5") (pinfunction "I4_5") (pintype "input"))
      (node (ref "IC2") (pin "14") (pinfunction "~{Q2}_14") (pintype "output"))
    )
    (net (code "219") (name "~{IR7}") (class "Default")
      (node (ref "IC12") (pin "4") (pinfunction "I3_4") (pintype "input"))
      (node (ref "IC2") (pin "1") (pinfunction "~{Q1}_1") (pintype "output"))
    )
    (net (code "220") (name "~{IR8}") (class "Default")
      (node (ref "IC1") (pin "8") (pinfunction "~{Q4}_8") (pintype "output"))
      (node (ref "IC12") (pin "3") (pinfunction "I2_3") (pintype "input"))
    )
    (net (code "221") (name "~{IR10}") (class "Default")
      (node (ref "IC1") (pin "14") (pinfunction "~{Q2}_14") (pintype "output"))
      (node (ref "IC17") (pin "5") (pinfunction "I1_5") (pintype "input"))
    )
    (net (code "222") (name "~{IR11}") (class "Default")
      (node (ref "IC1") (pin "1") (pinfunction "~{Q1}_1") (pintype "output"))
      (node (ref "IC17") (pin "10") (pinfunction "I1_10") (pintype "input"))
    )
    (net (code "223") (name "~{ISZ}") (class "Default")
      (node (ref "IC7") (pin "13") (pinfunction "Y2_13") (pintype "output"))
      (node (ref "PAD3") (pin "1") (pinfunction "P_1") (pintype "passive"))
    )
    (net (code "224") (name "~{JMP}") (class "Default")
      (node (ref "IC10") (pin "9") (pinfunction "I0_9") (pintype "input"))
      (node (ref "IC7") (pin "10") (pinfunction "Y5_10") (pintype "output"))
    )
    (net (code "225") (name "~{JMS}") (class "Default")
      (node (ref "IC10") (pin "10") (pinfunction "I1_10") (pintype "input"))
      (node (ref "IC7") (pin "11") (pinfunction "Y4_11") (pintype "output"))
    )
    (net (code "226") (name "~{MEMSEL}") (class "Default")
      (node (ref "CPU") (pin "37") (pinfunction "MEMSEL_37") (pintype "output"))
      (node (ref "IC10") (pin "13") (pinfunction "I1_13") (pintype "input"))
      (node (ref "IC36") (pin "12") (pinfunction "I0_12") (pintype "input"))
      (node (ref "IC36") (pin "9") (pinfunction "I0_9") (pintype "input"))
      (node (ref "IC38") (pin "20") (pinfunction "~{CS}_20") (pintype "input"))
      (node (ref "IC39") (pin "20") (pinfunction "~{CS}_20") (pintype "input"))
    )
    (net (code "227") (name "~{OE}") (class "Default")
      (node (ref "IC36") (pin "11") (pinfunction "O_11") (pintype "output"))
      (node (ref "IC38") (pin "22") (pinfunction "~{OE}_22") (pintype "input"))
      (node (ref "IC39") (pin "22") (pinfunction "~{OE}_22") (pintype "input"))
    )
    (net (code "228") (name "~{OPR}") (class "Default")
      (node (ref "IC4") (pin "4") (pinfunction "G2A_4") (pintype "input"))
      (node (ref "IC4") (pin "5") (pinfunction "G2B_5") (pintype "input"))
      (node (ref "IC7") (pin "7") (pinfunction "Y7_7") (pintype "output"))
    )
    (net (code "229") (name "~{OSRHLT}") (class "Default")
      (node (ref "IC4") (pin "9") (pinfunction "Y6_9") (pintype "output"))
      (node (ref "IC8") (pin "4") (pinfunction "I2_4") (pintype "input"))
    )
    (net (code "230") (name "~{OSR}") (class "Default")
      (node (ref "IC4") (pin "11") (pinfunction "Y4_11") (pintype "output"))
      (node (ref "IC8") (pin "2") (pinfunction "I1_2") (pintype "input"))
    )
    (net (code "231") (name "~{RDF}") (class "Default")
      (node (ref "IC14") (pin "14") (pinfunction "Y1_14") (pintype "output"))
      (node (ref "IC29") (pin "3") (pinfunction "I_3") (pintype "input"))
      (node (ref "IC36") (pin "2") (pinfunction "I1_2") (pintype "input"))
    )
    (net (code "232") (name "~{RESET}") (class "Default")
      (node (ref "CPU") (pin "7") (pinfunction "RESET_7") (pintype "input"))
      (node (ref "IC11") (pin "1") (pinfunction "CLR_1") (pintype "input"))
      (node (ref "IC18") (pin "1") (pinfunction "CLR_1") (pintype "input"))
      (node (ref "IC18") (pin "13") (pinfunction "CLR_13") (pintype "input"))
      (node (ref "IC26") (pin "5") (pinfunction "I1_5") (pintype "input"))
      (node (ref "IC35") (pin "13") (pinfunction "I1_13") (pintype "input"))
      (node (ref "IC40") (pin "1") (pinfunction "I0_1") (pintype "input"))
      (node (ref "IC42") (pin "1") (pinfunction "CLR_1") (pintype "input"))
      (node (ref "PAD7") (pin "1") (pinfunction "P_1") (pintype "passive"))
    )
    (net (code "233") (name "~{RIB}") (class "Default")
      (node (ref "IC14") (pin "12") (pinfunction "Y3_12") (pintype "output"))
      (node (ref "IC29") (pin "9") (pinfunction "I_9") (pintype "input"))
      (node (ref "IC35") (pin "9") (pinfunction "I0_9") (pintype "input"))
    )
    (net (code "234") (name "~{RIF}") (class "Default")
      (node (ref "IC14") (pin "13") (pinfunction "Y2_13") (pintype "output"))
      (node (ref "IC29") (pin "5") (pinfunction "I_5") (pintype "input"))
      (node (ref "IC34") (pin "1") (pinfunction "~{A}/B_1") (pintype "input"))
      (node (ref "IC36") (pin "1") (pinfunction "I0_1") (pintype "input"))
    )
    (net (code "235") (name "~{RMF}") (class "Default")
      (node (ref "IC14") (pin "11") (pinfunction "Y4_11") (pintype "output"))
      (node (ref "IC22") (pin "12") (pinfunction "I2_12") (pintype "input"))
      (node (ref "IC40") (pin "11") (pinfunction "I2_11") (pintype "input"))
      (node (ref "IC40") (pin "5") (pinfunction "I2_5") (pintype "input"))
      (node (ref "IC41") (pin "11") (pinfunction "A_11") (pintype "input"))
      (node (ref "IC48") (pin "1") (pinfunction "G_1") (pintype "input"))
      (node (ref "IC48") (pin "17") (pinfunction "A4_17") (pintype "input"))
      (node (ref "IC48") (pin "19") (pinfunction "G_19") (pintype "input"))
    )
    (net (code "236") (name "~{RTF}") (class "Default")
      (node (ref "IC13") (pin "10") (pinfunction "Y5_10") (pintype "output"))
      (node (ref "IC16") (pin "12") (pinfunction "I0_12") (pintype "input"))
      (node (ref "IC22") (pin "9") (pinfunction "I0_9") (pintype "input"))
      (node (ref "IC41") (pin "10") (pinfunction "B_10") (pintype "input"))
      (node (ref "IC46") (pin "1") (pinfunction "G_1") (pintype "input"))
      (node (ref "IC46") (pin "17") (pinfunction "A4_17") (pintype "input"))
      (node (ref "IC46") (pin "19") (pinfunction "G_19") (pintype "input"))
    )
    (net (code "237") (name "~{RUNHLT}") (class "Default")
      (node (ref "CPU") (pin "6") (pinfunction "RUNHLT_6") (pintype "input"))
      (node (ref "SV1") (pin "9") (pinfunction "9_9") (pintype "passive"))
    )
    (net (code "238") (name "~{SETZF}") (class "Default")
      (node (ref "IC18") (pin "10") (pinfunction "PRE_10") (pintype "input"))
      (node (ref "IC20") (pin "1") (pinfunction "CLR_1") (pintype "input"))
      (node (ref "IC22") (pin "6") (pinfunction "O_6") (pintype "output"))
    )
    (net (code "239") (name "~{SINT}") (class "Default")
      (node (ref "IC14") (pin "10") (pinfunction "Y5_10") (pintype "output"))
      (node (ref "IC16") (pin "9") (pinfunction "I0_9") (pintype "input"))
    )
    (net (code "240") (name "~{SKP}") (class "Default")
      (node (ref "CPU") (pin "35") (pinfunction "SKP_35") (pintype "input"))
      (node (ref "IC29") (pin "12") (pinfunction "O_12") (pintype "open_collector"))
      (node (ref "SV1") (pin "24") (pinfunction "24_24") (pintype "passive"))
    )
    (net (code "241") (name "~{SUF}") (class "Default")
      (node (ref "IC11") (pin "10") (pinfunction "PRE_10") (pintype "input"))
      (node (ref "IC14") (pin "7") (pinfunction "Y7_7") (pintype "output"))
      (node (ref "IC22") (pin "13") (pinfunction "I3_13") (pintype "input"))
    )
    (net (code "242") (name "~{SWSEL}") (class "Default")
      (node (ref "CPU") (pin "31") (pinfunction "SWSEL_31") (pintype "output"))
      (node (ref "PAD8") (pin "1") (pinfunction "P_1") (pintype "passive"))
    )
    (net (code "243") (name "~{TAD}") (class "Default")
      (node (ref "IC7") (pin "14") (pinfunction "Y1_14") (pintype "output"))
      (node (ref "PAD2") (pin "1") (pinfunction "P_1") (pintype "passive"))
    )
    (net (code "244") (name "~{UIF}") (class "Default")
      (node (ref "IC11") (pin "6") (pinfunction "~{Q}_6") (pintype "output"))
      (node (ref "IC16") (pin "10") (pinfunction "I1_10") (pintype "input"))
    )
    (net (code "245") (name "~{WAIT}") (class "Default")
      (node (ref "CPU") (pin "11") (pinfunction "WAIT_11") (pintype "input"))
      (node (ref "SV1") (pin "26") (pinfunction "26_26") (pintype "passive"))
    )
    (net (code "246") (name "~{WE}") (class "Default")
      (node (ref "IC36") (pin "8") (pinfunction "O_8") (pintype "output"))
      (node (ref "IC38") (pin "27") (pinfunction "~{WE}_27") (pintype "input"))
      (node (ref "IC39") (pin "27") (pinfunction "~{WE}_27") (pintype "input"))
    )
    (net (code "247") (name "~{XTA}") (class "Default")
      (node (ref "IC26") (pin "8") (pinfunction "O_8") (pintype "output"))
      (node (ref "IC35") (pin "10") (pinfunction "I1_10") (pintype "input"))
      (node (ref "IC35") (pin "2") (pinfunction "I1_2") (pintype "input"))
      (node (ref "IC35") (pin "5") (pinfunction "I1_5") (pintype "input"))
      (node (ref "IC36") (pin "13") (pinfunction "I1_13") (pintype "input"))
    )
    (net (code "248") (name "~{XTB}") (class "Default")
      (node (ref "IC16") (pin "13") (pinfunction "I1_13") (pintype "input"))
      (node (ref "IC26") (pin "11") (pinfunction "O_11") (pintype "output"))
      (node (ref "IC36") (pin "10") (pinfunction "I1_10") (pintype "input"))
    )
  )
)
